# M7104BYA.net
KiCad netlist of a schematic drawn in EAGLE
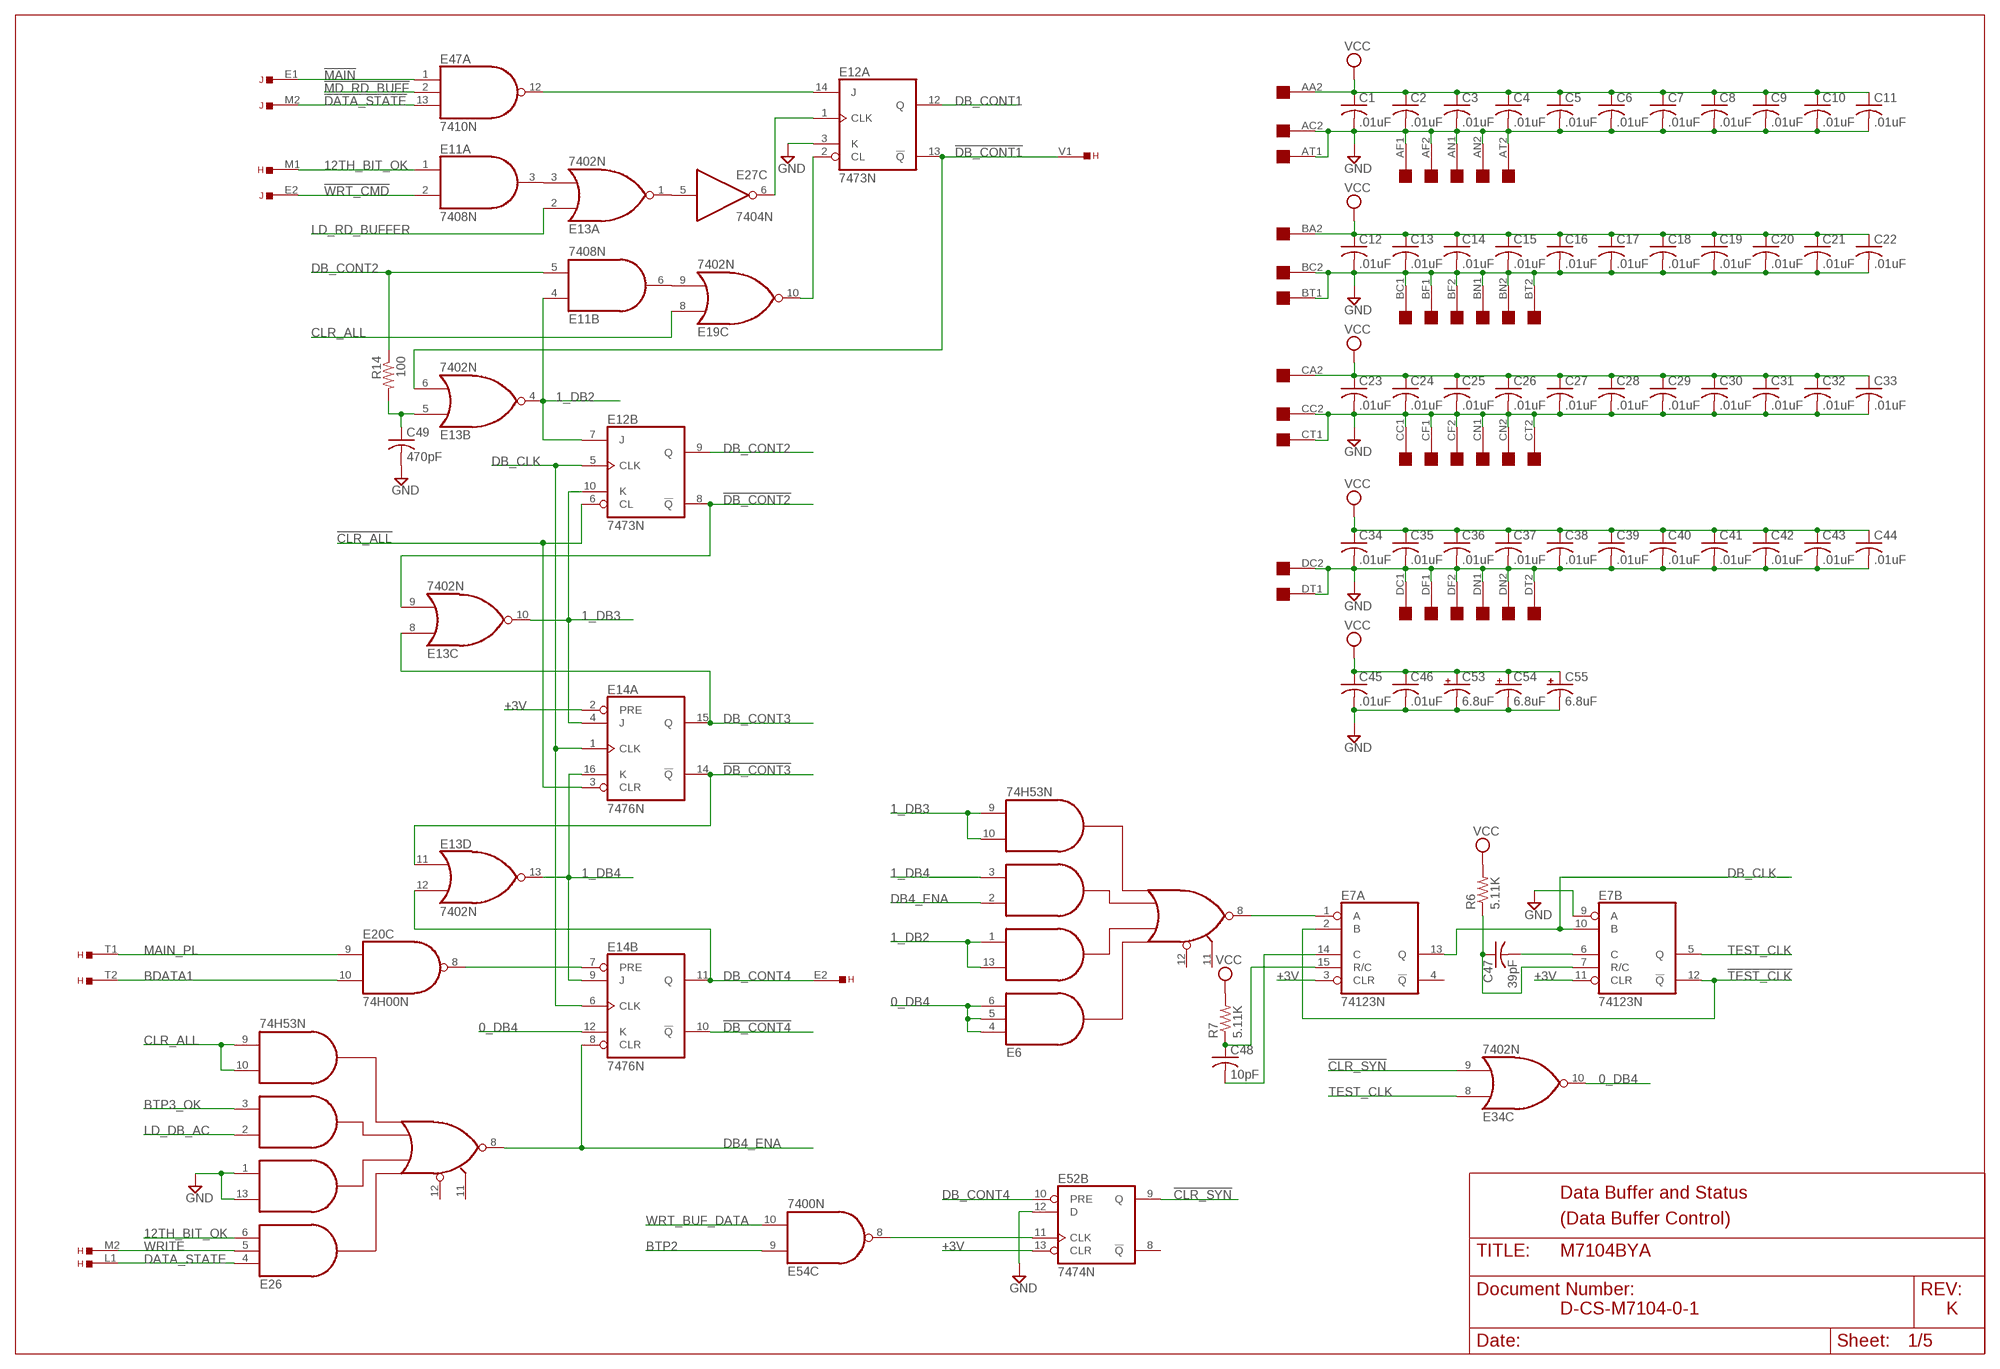
[diagram p0: schematic, sheet 1]
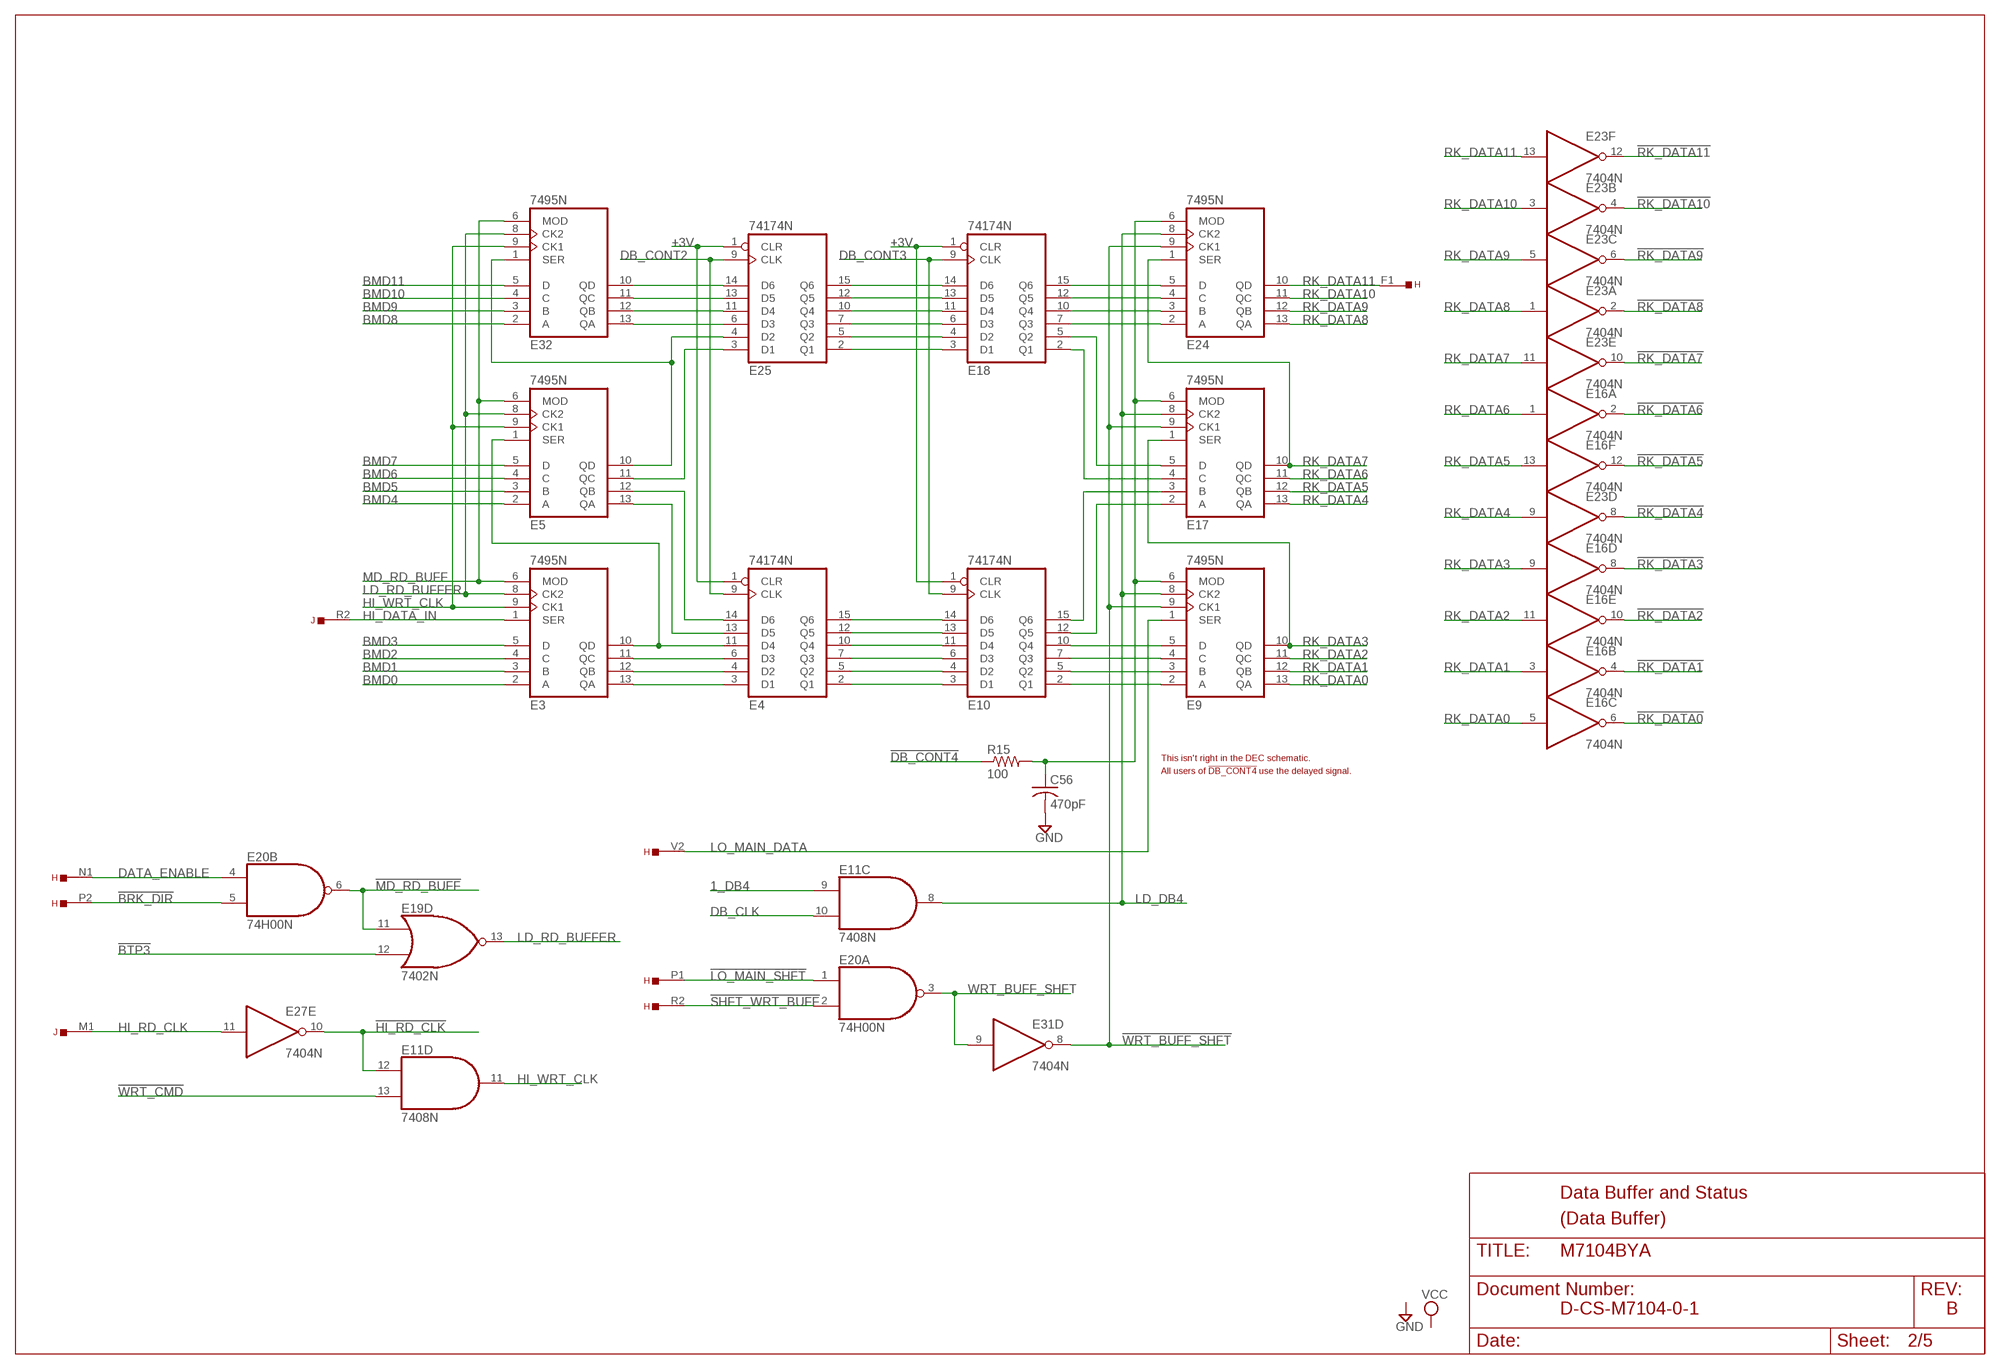
[diagram p1: schematic, sheet 2]
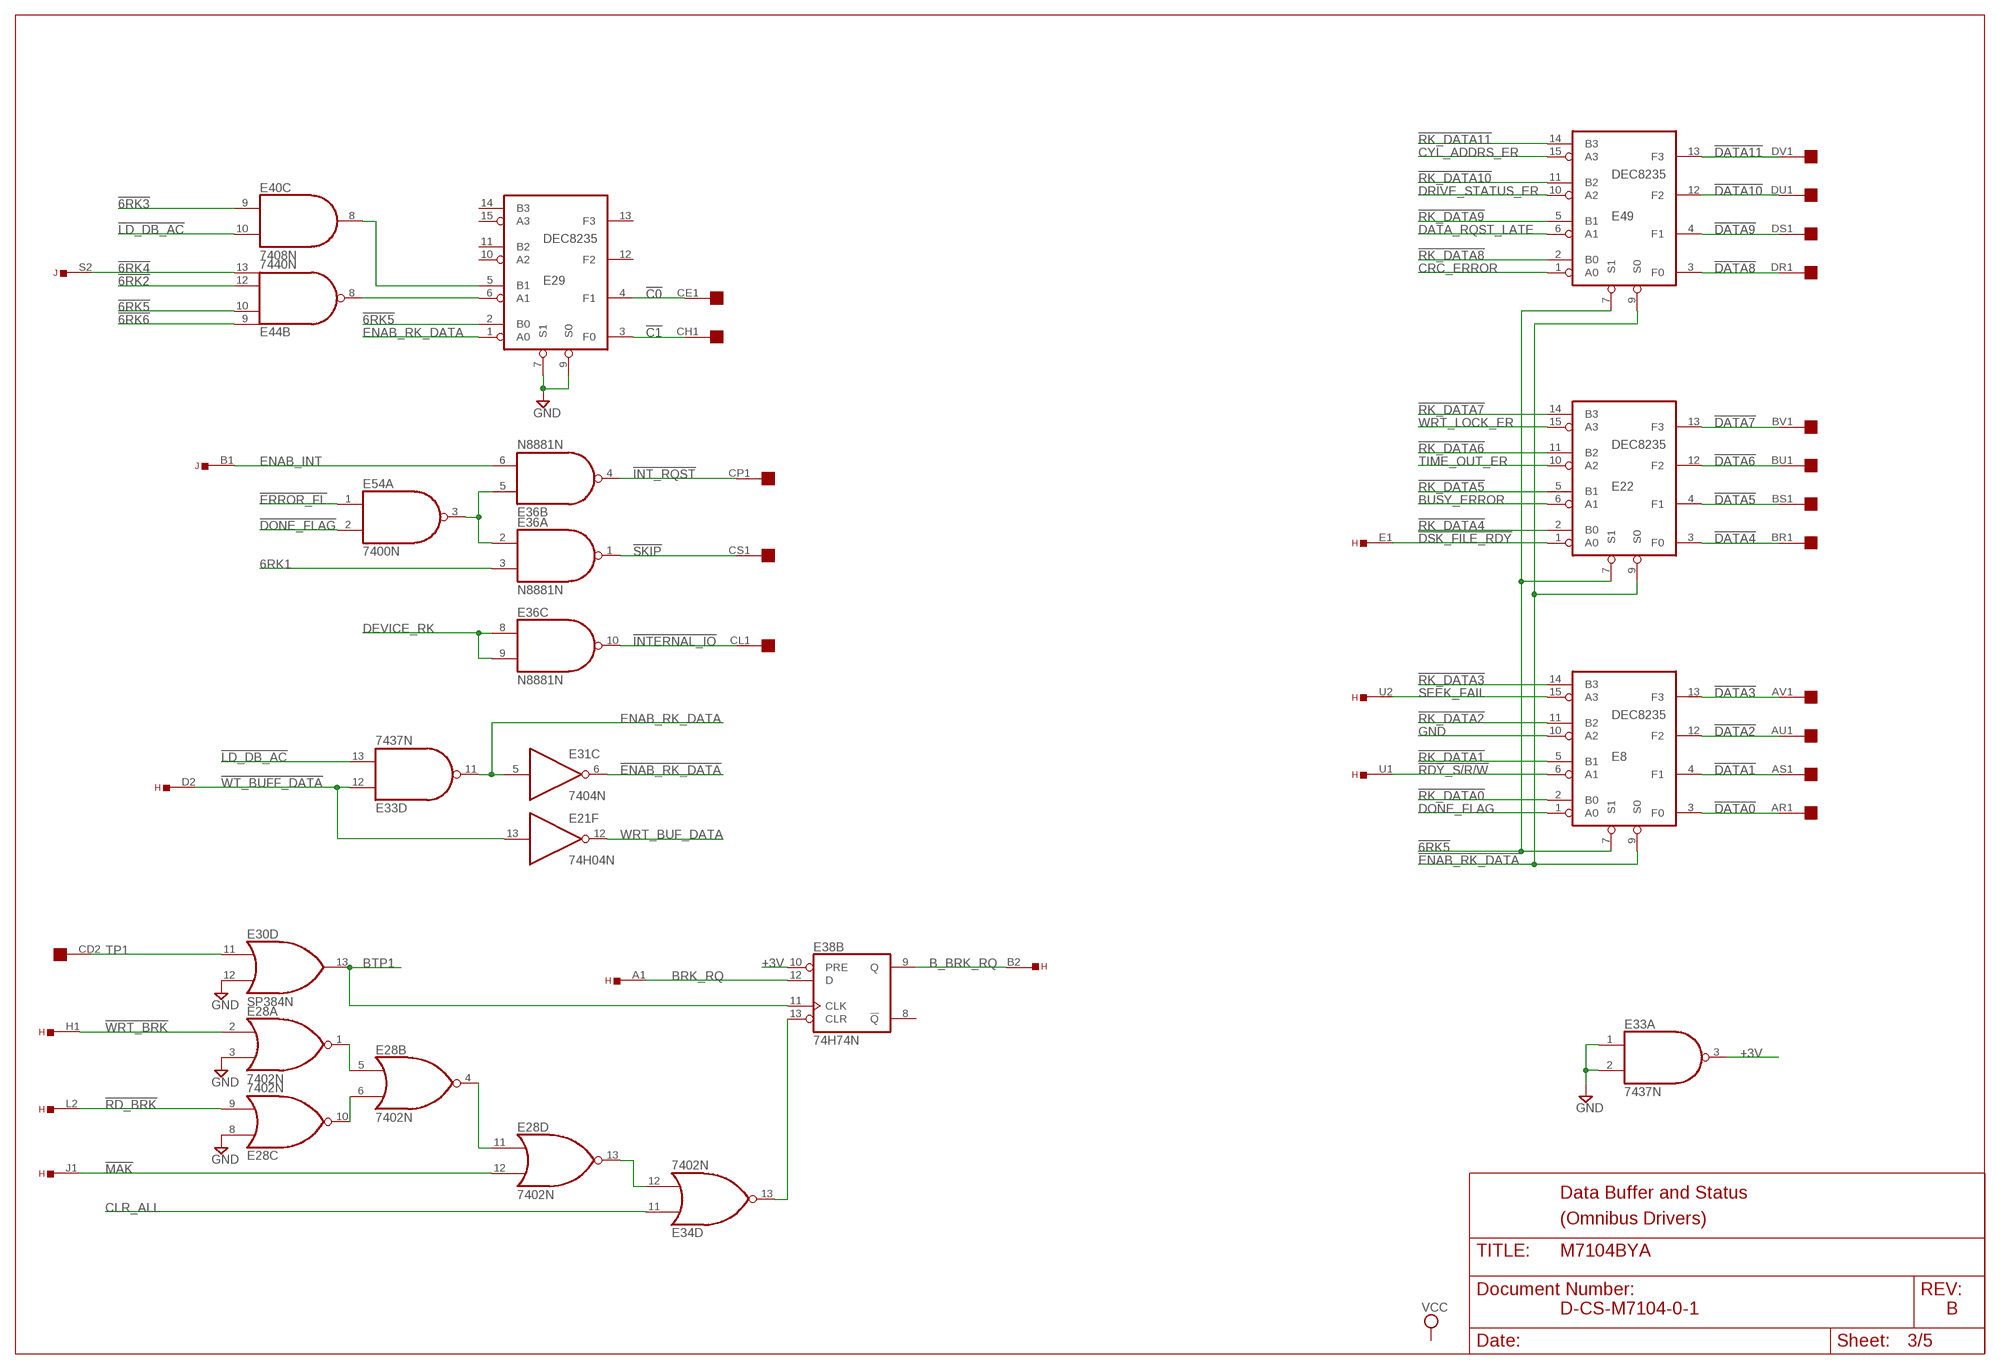
[diagram p2: schematic, sheet 3]
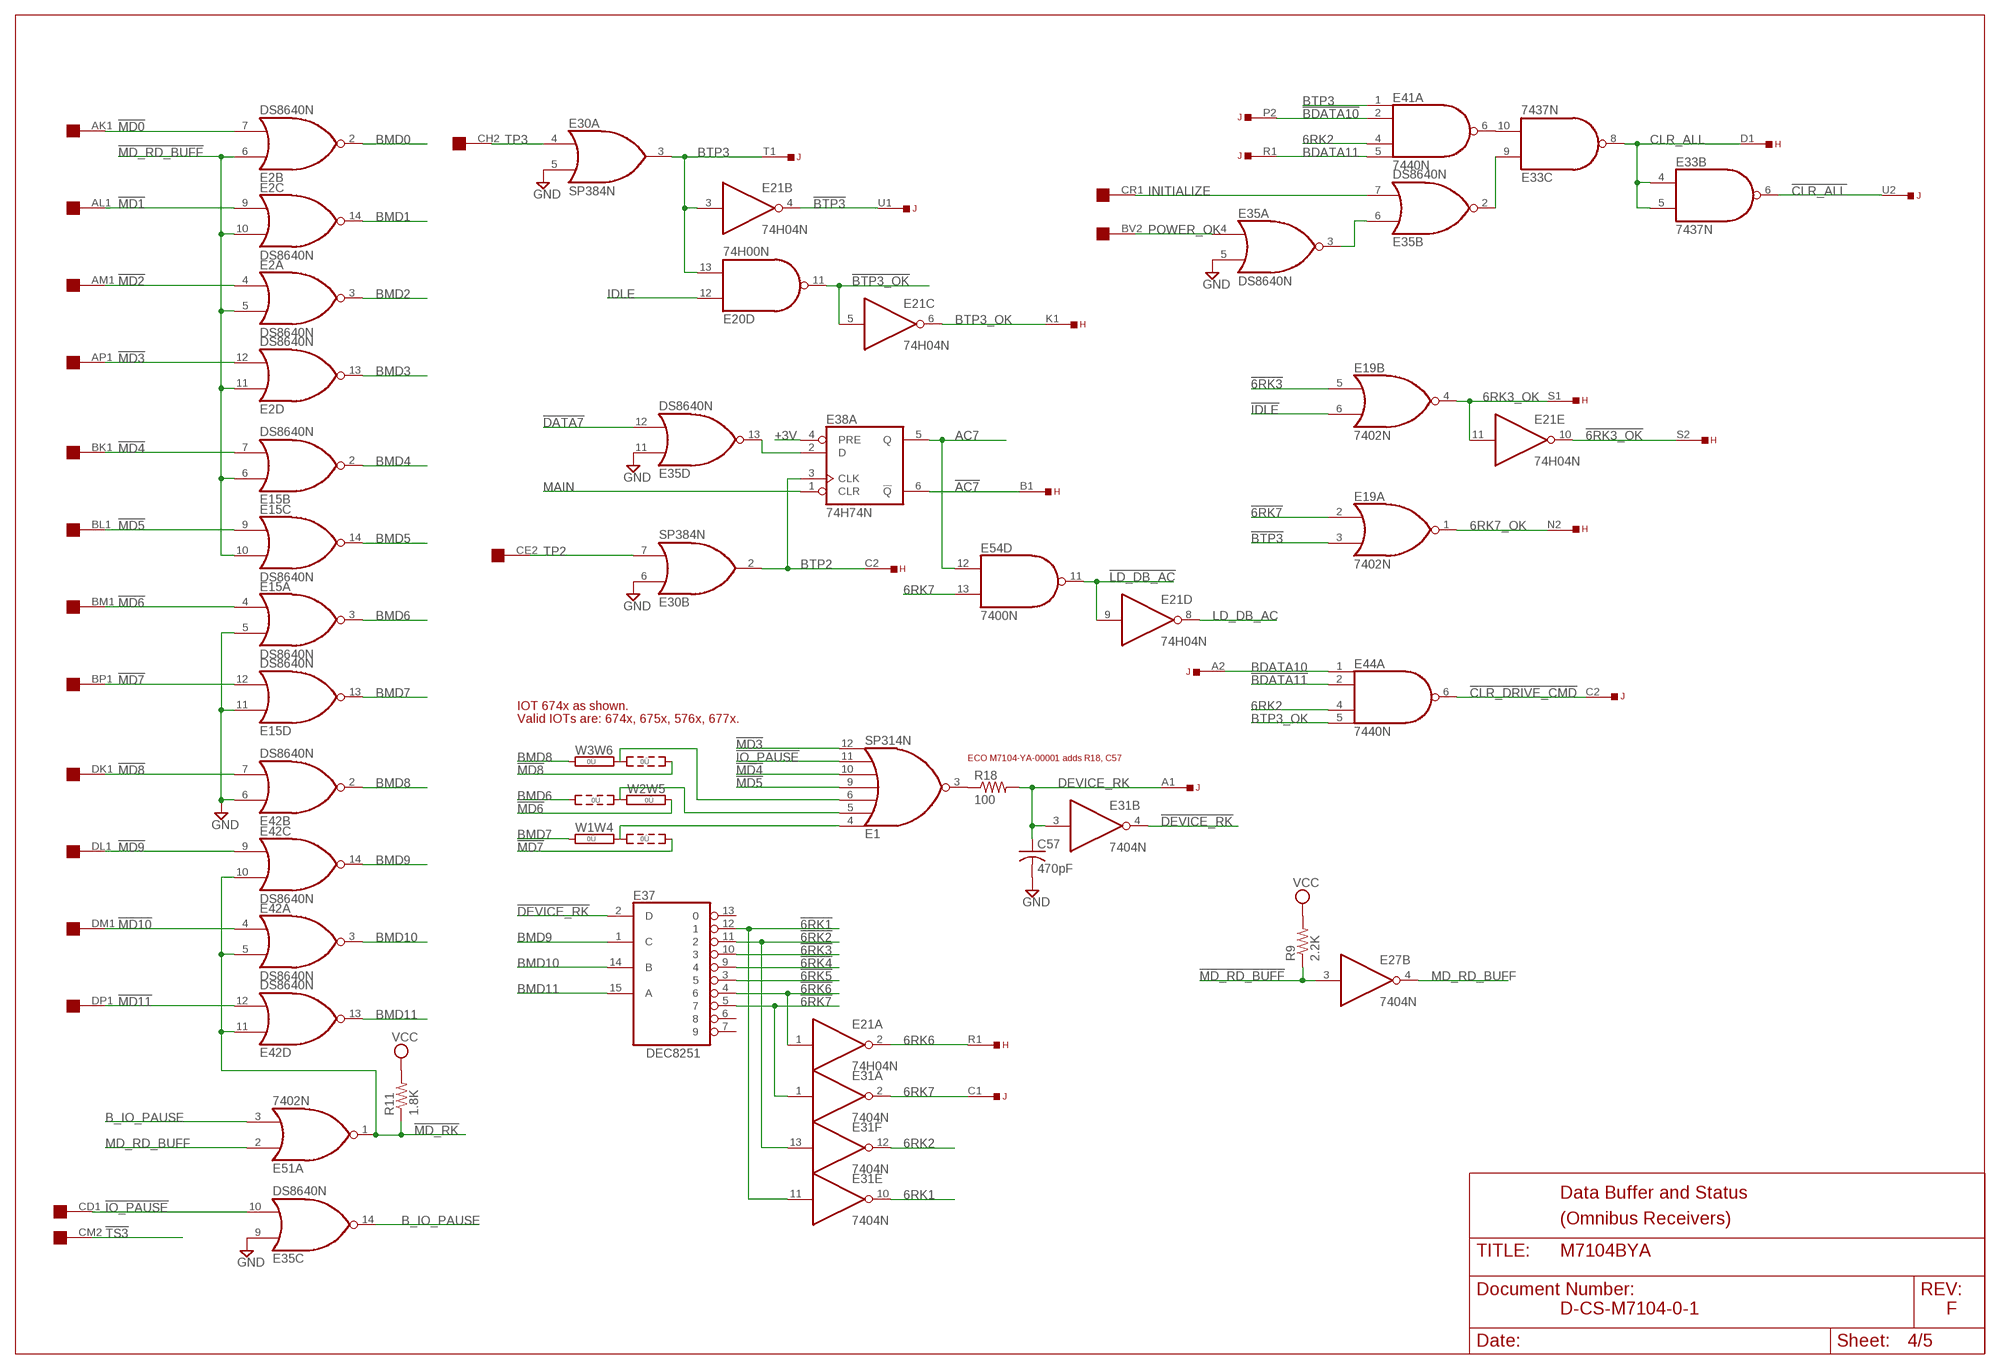
[diagram p3: schematic, sheet 4]
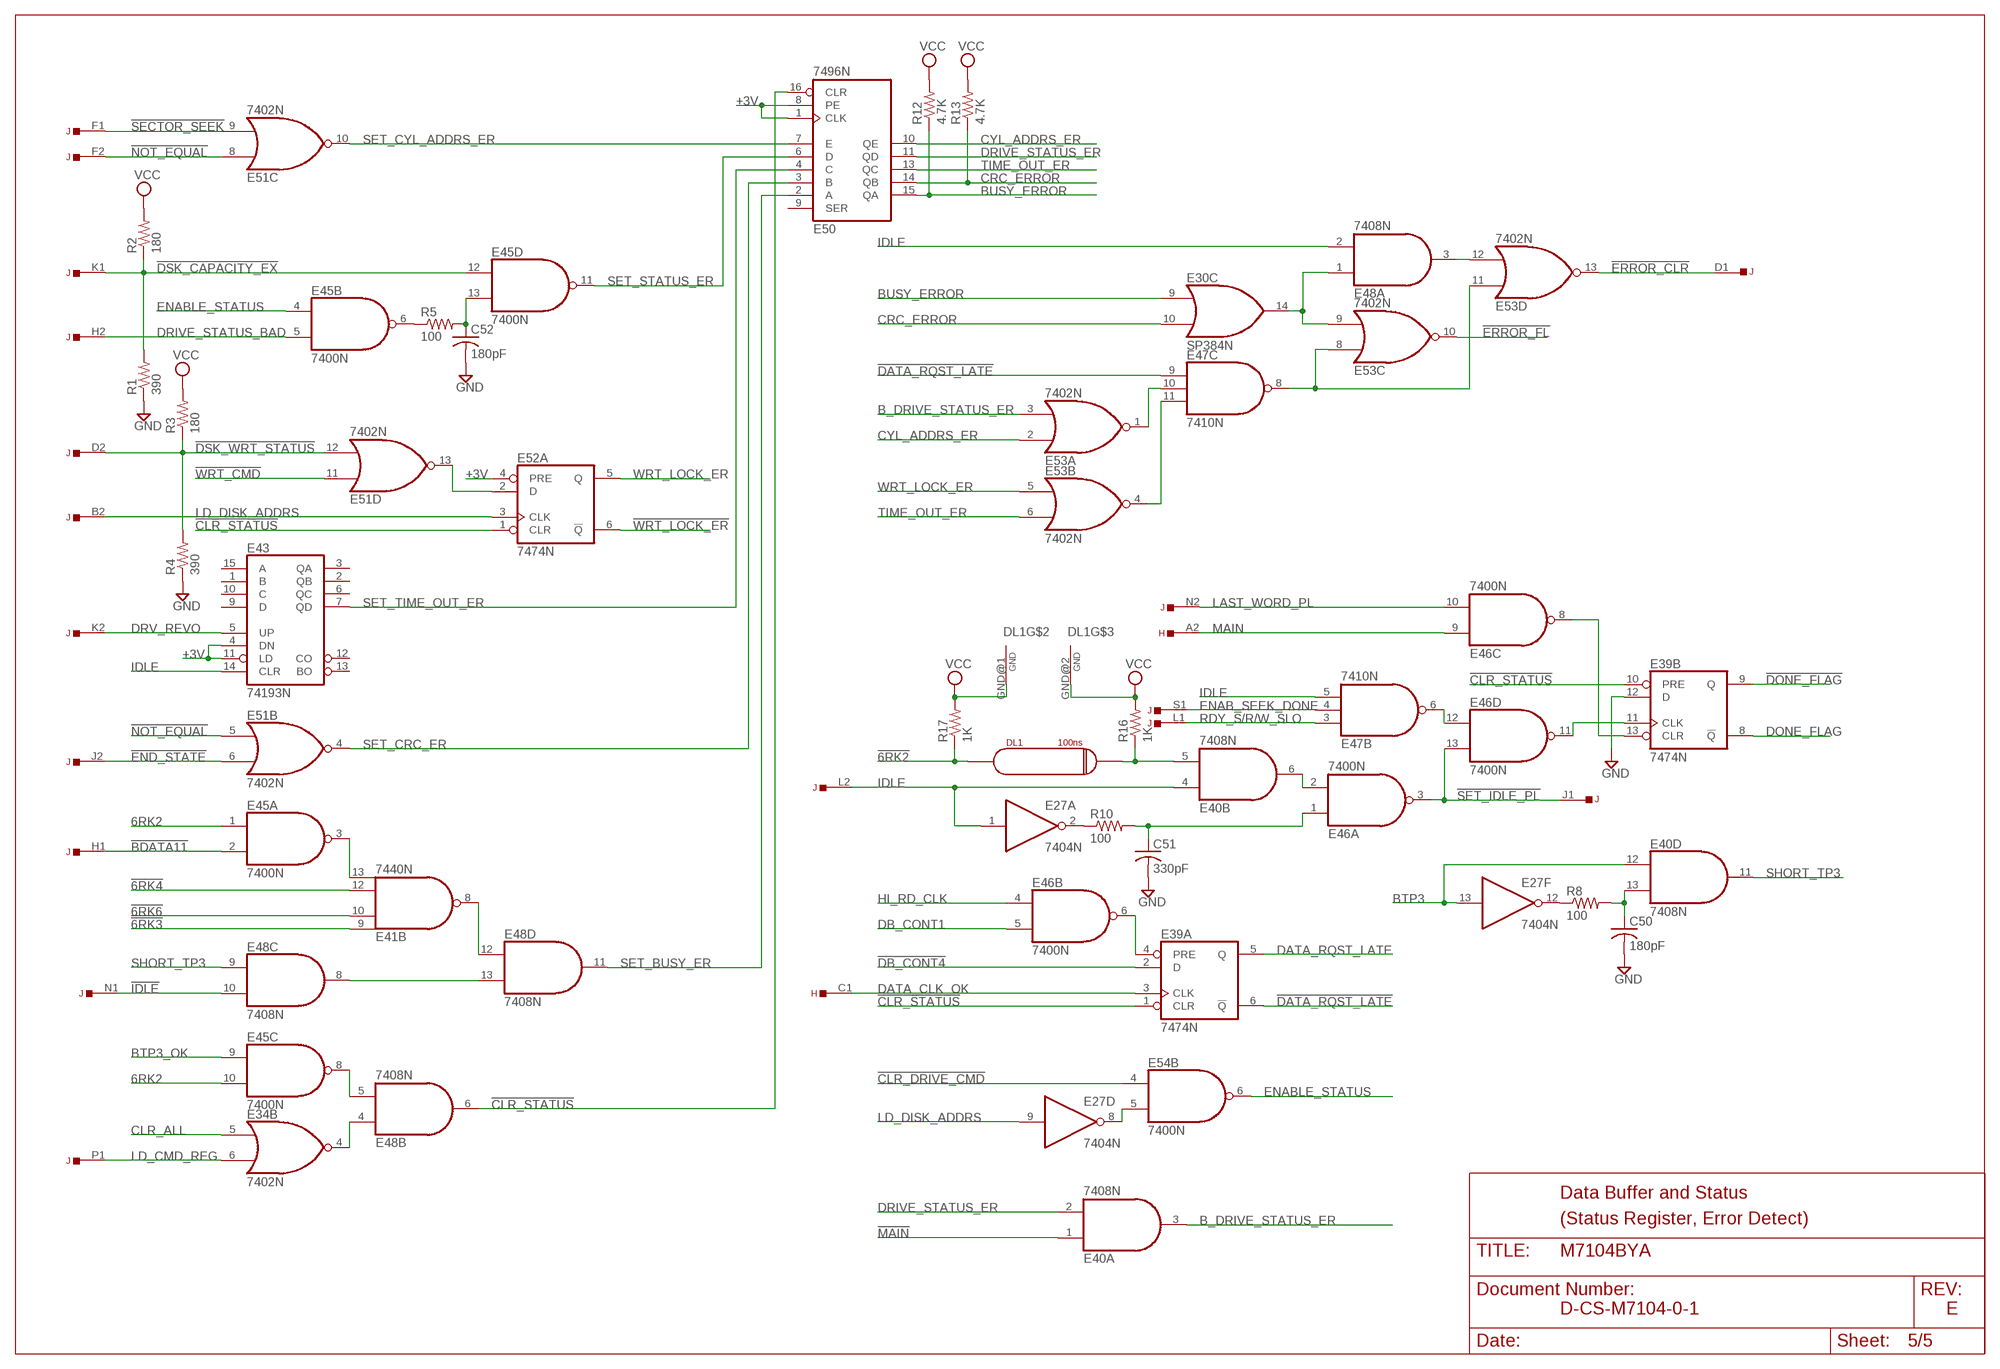
[diagram p4: schematic, sheet 5]

(export (version "E")
  (design (tool "Eeschema 10.0.6"))
  (components
    (comp (ref "C50")
      (value "180pF")
      (footprint "eagle-import:C063-025X075")
      (libsource (lib "eagle-import") (part "C-US"))
    )
    (comp (ref "C51")
      (value "330pF")
      (footprint "eagle-import:C063-025X075")
      (libsource (lib "eagle-import") (part "C-US"))
    )
    (comp (ref "C52")
      (value "180pF")
      (footprint "eagle-import:C063-025X075")
      (libsource (lib "eagle-import") (part "C-US"))
    )
    (comp (ref "DL1")
      (value "100ns")
      (footprint "eagle-import:RCL-L-XX-22")
      (libsource (lib "eagle-import") (part "RC-L-22"))
    )
    (comp (ref "E27")
      (value "7404N")
      (footprint "eagle-import:DIL14")
      (libsource (lib "eagle-import") (part "7404N"))
    )
    (comp (ref "E30")
      (value "SP384N")
      (footprint "eagle-import:DIL14")
      (libsource (lib "eagle-import") (part "SP384N"))
    )
    (comp (ref "E34")
      (value "7402N")
      (footprint "eagle-import:DIL14")
      (libsource (lib "eagle-import") (part "7402N"))
    )
    (comp (ref "E39")
      (value "7474N")
      (footprint "eagle-import:DIL14")
      (libsource (lib "eagle-import") (part "7474NS"))
    )
    (comp (ref "E40")
      (value "7408N")
      (footprint "eagle-import:DIL14")
      (libsource (lib "eagle-import") (part "7408NS"))
    )
    (comp (ref "E41")
      (value "7440N")
      (footprint "eagle-import:DIL14")
      (libsource (lib "eagle-import") (part "7440N"))
    )
    (comp (ref "E43")
      (value "74193N")
      (footprint "eagle-import:DIL16")
      (libsource (lib "eagle-import") (part "74193N"))
    )
    (comp (ref "E45")
      (value "7400N")
      (footprint "eagle-import:DIL14")
      (libsource (lib "eagle-import") (part "7400N"))
    )
    (comp (ref "E46")
      (value "7400N")
      (footprint "eagle-import:DIL14")
      (libsource (lib "eagle-import") (part "7400N"))
    )
    (comp (ref "E47")
      (value "7410N")
      (footprint "eagle-import:DIL14")
      (libsource (lib "eagle-import") (part "7410N"))
    )
    (comp (ref "E48")
      (value "7408N")
      (footprint "eagle-import:DIL14")
      (libsource (lib "eagle-import") (part "7408NS"))
    )
    (comp (ref "E50")
      (value "7496N")
      (footprint "eagle-import:DIL16")
      (libsource (lib "eagle-import") (part "7496NLS"))
    )
    (comp (ref "E51")
      (value "7402N")
      (footprint "eagle-import:DIL14")
      (libsource (lib "eagle-import") (part "7402N"))
    )
    (comp (ref "E52")
      (value "7474N")
      (footprint "eagle-import:DIL14")
      (libsource (lib "eagle-import") (part "7474NS"))
    )
    (comp (ref "E53")
      (value "7402N")
      (footprint "eagle-import:DIL14")
      (libsource (lib "eagle-import") (part "7402N"))
    )
    (comp (ref "E54")
      (value "7400N")
      (footprint "eagle-import:DIL14")
      (libsource (lib "eagle-import") (part "7400N"))
    )
    (comp (ref "H")
      (value "EDGE-TOP")
      (footprint "eagle-import:EDGE-CON2")
      (libsource (lib "eagle-import") (part "EDGE-TOP"))
    )
    (comp (ref "J")
      (value "EDGE-TOP")
      (footprint "eagle-import:EDGE-CON2")
      (libsource (lib "eagle-import") (part "EDGE-TOP"))
    )
    (comp (ref "R1")
      (value "390")
      (footprint "eagle-import:0207_10")
      (libsource (lib "eagle-import") (part "R-US_0207/10"))
    )
    (comp (ref "R2")
      (value "180")
      (footprint "eagle-import:0207_10")
      (libsource (lib "eagle-import") (part "R-US_0207/10"))
    )
    (comp (ref "R3")
      (value "180")
      (footprint "eagle-import:0207_10")
      (libsource (lib "eagle-import") (part "R-US_0207/10"))
    )
    (comp (ref "R4")
      (value "390")
      (footprint "eagle-import:0207_10")
      (libsource (lib "eagle-import") (part "R-US_0207/10"))
    )
    (comp (ref "R5")
      (value "100")
      (footprint "eagle-import:0207_10")
      (libsource (lib "eagle-import") (part "R-US_0207/10"))
    )
    (comp (ref "R8")
      (value "100")
      (footprint "eagle-import:0207_10")
      (libsource (lib "eagle-import") (part "R-US_0207/10"))
    )
    (comp (ref "R10")
      (value "100")
      (footprint "eagle-import:0207_10")
      (libsource (lib "eagle-import") (part "R-US_0207/10"))
    )
    (comp (ref "R12")
      (value "4.7K")
      (footprint "eagle-import:0207_10")
      (libsource (lib "eagle-import") (part "R-US_0207/10"))
    )
    (comp (ref "R13")
      (value "4.7K")
      (footprint "eagle-import:0207_10")
      (libsource (lib "eagle-import") (part "R-US_0207/10"))
    )
    (comp (ref "R16")
      (value "1K")
      (footprint "eagle-import:0207_10")
      (libsource (lib "eagle-import") (part "R-US_0207/10"))
    )
    (comp (ref "R17")
      (value "1K")
      (footprint "eagle-import:0207_10")
      (libsource (lib "eagle-import") (part "R-US_0207/10"))
    )
    (comp (ref "C57")
      (value "470pF")
      (footprint "eagle-import:C063-025X075")
      (libsource (lib "eagle-import") (part "C-US"))
    )
    (comp (ref "E1")
      (value "SP314N")
      (footprint "eagle-import:DIL14")
      (libsource (lib "eagle-import") (part "SP314N"))
    )
    (comp (ref "E2")
      (value "DS8640N")
      (footprint "eagle-import:DIL14")
      (libsource (lib "eagle-import") (part "DS8640N"))
    )
    (comp (ref "E15")
      (value "DS8640N")
      (footprint "eagle-import:DIL14")
      (libsource (lib "eagle-import") (part "DS8640N"))
    )
    (comp (ref "E19")
      (value "7402N")
      (footprint "eagle-import:DIL14")
      (libsource (lib "eagle-import") (part "7402N"))
    )
    (comp (ref "E20")
      (value "74H00N")
      (footprint "eagle-import:DIL14")
      (libsource (lib "eagle-import") (part "7400NS"))
    )
    (comp (ref "E21")
      (value "74H04N")
      (footprint "eagle-import:DIL14")
      (libsource (lib "eagle-import") (part "7404N"))
    )
    (comp (ref "E31")
      (value "7404N")
      (footprint "eagle-import:DIL14")
      (libsource (lib "eagle-import") (part "7404N"))
    )
    (comp (ref "E33")
      (value "7437N")
      (footprint "eagle-import:DIL14")
      (libsource (lib "eagle-import") (part "7437N"))
    )
    (comp (ref "E35")
      (value "DS8640N")
      (footprint "eagle-import:DIL14")
      (libsource (lib "eagle-import") (part "DS8640N"))
    )
    (comp (ref "E37")
      (value "DEC8251")
      (footprint "eagle-import:DIL16")
      (libsource (lib "eagle-import") (part "DEC8251"))
    )
    (comp (ref "E38")
      (value "74H74N")
      (footprint "eagle-import:DIL14")
      (libsource (lib "eagle-import") (part "7474NS"))
    )
    (comp (ref "E42")
      (value "DS8640N")
      (footprint "eagle-import:DIL14")
      (libsource (lib "eagle-import") (part "DS8640N"))
    )
    (comp (ref "E44")
      (value "7440N")
      (footprint "eagle-import:DIL14")
      (libsource (lib "eagle-import") (part "7440N"))
    )
    (comp (ref "OMNIBUS")
      (value "QUAD")
      (footprint "eagle-import:EDGE-CON8")
      (libsource (lib "eagle-import") (part "QUAD"))
    )
    (comp (ref "R9")
      (value "2.2K")
      (footprint "eagle-import:0207_10")
      (libsource (lib "eagle-import") (part "R-US_0207/10"))
    )
    (comp (ref "R11")
      (value "1.8K")
      (footprint "eagle-import:0207_10")
      (libsource (lib "eagle-import") (part "R-US_0207/10"))
    )
    (comp (ref "R18")
      (value "100")
      (footprint "eagle-import:0207_10")
      (libsource (lib "eagle-import") (part "R-US_0207/10"))
    )
    (comp (ref "W1W4")
      (value "0R2")
      (footprint "eagle-import:0R2_10")
      (libsource (lib "eagle-import") (part "0R2"))
    )
    (comp (ref "W2W5")
      (value "0R2")
      (footprint "eagle-import:0R2_10")
      (libsource (lib "eagle-import") (part "0R2"))
    )
    (comp (ref "W3W6")
      (value "0R2")
      (footprint "eagle-import:0R2_10")
      (libsource (lib "eagle-import") (part "0R2"))
    )
    (comp (ref "C1")
      (value ".01uF")
      (footprint "eagle-import:C063-025X075")
      (libsource (lib "eagle-import") (part "C-US"))
    )
    (comp (ref "C2")
      (value ".01uF")
      (footprint "eagle-import:C063-025X075")
      (libsource (lib "eagle-import") (part "C-US"))
    )
    (comp (ref "C3")
      (value ".01uF")
      (footprint "eagle-import:C063-025X075")
      (libsource (lib "eagle-import") (part "C-US"))
    )
    (comp (ref "C4")
      (value ".01uF")
      (footprint "eagle-import:C063-025X075")
      (libsource (lib "eagle-import") (part "C-US"))
    )
    (comp (ref "C5")
      (value ".01uF")
      (footprint "eagle-import:C063-025X075")
      (libsource (lib "eagle-import") (part "C-US"))
    )
    (comp (ref "C6")
      (value ".01uF")
      (footprint "eagle-import:C063-025X075")
      (libsource (lib "eagle-import") (part "C-US"))
    )
    (comp (ref "C7")
      (value ".01uF")
      (footprint "eagle-import:C063-025X075")
      (libsource (lib "eagle-import") (part "C-US"))
    )
    (comp (ref "C8")
      (value ".01uF")
      (footprint "eagle-import:C063-025X075")
      (libsource (lib "eagle-import") (part "C-US"))
    )
    (comp (ref "C9")
      (value ".01uF")
      (footprint "eagle-import:C063-025X075")
      (libsource (lib "eagle-import") (part "C-US"))
    )
    (comp (ref "C10")
      (value ".01uF")
      (footprint "eagle-import:C063-025X075")
      (libsource (lib "eagle-import") (part "C-US"))
    )
    (comp (ref "C11")
      (value ".01uF")
      (footprint "eagle-import:C063-025X075")
      (libsource (lib "eagle-import") (part "C-US"))
    )
    (comp (ref "C12")
      (value ".01uF")
      (footprint "eagle-import:C063-025X075")
      (libsource (lib "eagle-import") (part "C-US"))
    )
    (comp (ref "C13")
      (value ".01uF")
      (footprint "eagle-import:C063-025X075")
      (libsource (lib "eagle-import") (part "C-US"))
    )
    (comp (ref "C14")
      (value ".01uF")
      (footprint "eagle-import:C063-025X075")
      (libsource (lib "eagle-import") (part "C-US"))
    )
    (comp (ref "C15")
      (value ".01uF")
      (footprint "eagle-import:C063-025X075")
      (libsource (lib "eagle-import") (part "C-US"))
    )
    (comp (ref "C16")
      (value ".01uF")
      (footprint "eagle-import:C063-025X075")
      (libsource (lib "eagle-import") (part "C-US"))
    )
    (comp (ref "C17")
      (value ".01uF")
      (footprint "eagle-import:C063-025X075")
      (libsource (lib "eagle-import") (part "C-US"))
    )
    (comp (ref "C18")
      (value ".01uF")
      (footprint "eagle-import:C063-025X075")
      (libsource (lib "eagle-import") (part "C-US"))
    )
    (comp (ref "C19")
      (value ".01uF")
      (footprint "eagle-import:C063-025X075")
      (libsource (lib "eagle-import") (part "C-US"))
    )
    (comp (ref "C20")
      (value ".01uF")
      (footprint "eagle-import:C063-025X075")
      (libsource (lib "eagle-import") (part "C-US"))
    )
    (comp (ref "C21")
      (value ".01uF")
      (footprint "eagle-import:C063-025X075")
      (libsource (lib "eagle-import") (part "C-US"))
    )
    (comp (ref "C22")
      (value ".01uF")
      (footprint "eagle-import:C063-025X075")
      (libsource (lib "eagle-import") (part "C-US"))
    )
    (comp (ref "C23")
      (value ".01uF")
      (footprint "eagle-import:C063-025X075")
      (libsource (lib "eagle-import") (part "C-US"))
    )
    (comp (ref "C24")
      (value ".01uF")
      (footprint "eagle-import:C063-025X075")
      (libsource (lib "eagle-import") (part "C-US"))
    )
    (comp (ref "C25")
      (value ".01uF")
      (footprint "eagle-import:C063-025X075")
      (libsource (lib "eagle-import") (part "C-US"))
    )
    (comp (ref "C26")
      (value ".01uF")
      (footprint "eagle-import:C063-025X075")
      (libsource (lib "eagle-import") (part "C-US"))
    )
    (comp (ref "C27")
      (value ".01uF")
      (footprint "eagle-import:C063-025X075")
      (libsource (lib "eagle-import") (part "C-US"))
    )
    (comp (ref "C28")
      (value ".01uF")
      (footprint "eagle-import:C063-025X075")
      (libsource (lib "eagle-import") (part "C-US"))
    )
    (comp (ref "C29")
      (value ".01uF")
      (footprint "eagle-import:C063-025X075")
      (libsource (lib "eagle-import") (part "C-US"))
    )
    (comp (ref "C30")
      (value ".01uF")
      (footprint "eagle-import:C063-025X075")
      (libsource (lib "eagle-import") (part "C-US"))
    )
    (comp (ref "C31")
      (value ".01uF")
      (footprint "eagle-import:C063-025X075")
      (libsource (lib "eagle-import") (part "C-US"))
    )
    (comp (ref "C32")
      (value ".01uF")
      (footprint "eagle-import:C063-025X075")
      (libsource (lib "eagle-import") (part "C-US"))
    )
    (comp (ref "C33")
      (value ".01uF")
      (footprint "eagle-import:C063-025X075")
      (libsource (lib "eagle-import") (part "C-US"))
    )
    (comp (ref "C34")
      (value ".01uF")
      (footprint "eagle-import:C063-025X075")
      (libsource (lib "eagle-import") (part "C-US"))
    )
    (comp (ref "C35")
      (value ".01uF")
      (footprint "eagle-import:C063-025X075")
      (libsource (lib "eagle-import") (part "C-US"))
    )
    (comp (ref "C36")
      (value ".01uF")
      (footprint "eagle-import:C063-025X075")
      (libsource (lib "eagle-import") (part "C-US"))
    )
    (comp (ref "C37")
      (value ".01uF")
      (footprint "eagle-import:C063-025X075")
      (libsource (lib "eagle-import") (part "C-US"))
    )
    (comp (ref "C38")
      (value ".01uF")
      (footprint "eagle-import:C063-025X075")
      (libsource (lib "eagle-import") (part "C-US"))
    )
    (comp (ref "C39")
      (value ".01uF")
      (footprint "eagle-import:C063-025X075")
      (libsource (lib "eagle-import") (part "C-US"))
    )
    (comp (ref "C40")
      (value ".01uF")
      (footprint "eagle-import:C063-025X075")
      (libsource (lib "eagle-import") (part "C-US"))
    )
    (comp (ref "C41")
      (value ".01uF")
      (footprint "eagle-import:C063-025X075")
      (libsource (lib "eagle-import") (part "C-US"))
    )
    (comp (ref "C42")
      (value ".01uF")
      (footprint "eagle-import:C063-025X075")
      (libsource (lib "eagle-import") (part "C-US"))
    )
    (comp (ref "C43")
      (value ".01uF")
      (footprint "eagle-import:C063-025X075")
      (libsource (lib "eagle-import") (part "C-US"))
    )
    (comp (ref "C44")
      (value ".01uF")
      (footprint "eagle-import:C063-025X075")
      (libsource (lib "eagle-import") (part "C-US"))
    )
    (comp (ref "C45")
      (value ".01uF")
      (footprint "eagle-import:C063-025X075")
      (libsource (lib "eagle-import") (part "C-US"))
    )
    (comp (ref "C46")
      (value ".01uF")
      (footprint "eagle-import:C063-025X075")
      (libsource (lib "eagle-import") (part "C-US"))
    )
    (comp (ref "C47")
      (value "39pF")
      (footprint "eagle-import:C063-025X075")
      (libsource (lib "eagle-import") (part "C-US"))
    )
    (comp (ref "C48")
      (value "10pF")
      (footprint "eagle-import:C063-025X075")
      (libsource (lib "eagle-import") (part "C-US"))
    )
    (comp (ref "C49")
      (value "470pF")
      (footprint "eagle-import:C063-025X075")
      (libsource (lib "eagle-import") (part "C-US"))
    )
    (comp (ref "C53")
      (value "6.8uF")
      (footprint "eagle-import:E12-8")
      (libsource (lib "eagle-import") (part "CPOL-USE20-8AXIAL"))
    )
    (comp (ref "C54")
      (value "6.8uF")
      (footprint "eagle-import:E12-8")
      (libsource (lib "eagle-import") (part "CPOL-USE20-8AXIAL"))
    )
    (comp (ref "C55")
      (value "6.8uF")
      (footprint "eagle-import:E12-8")
      (libsource (lib "eagle-import") (part "CPOL-USE20-8AXIAL"))
    )
    (comp (ref "E6")
      (value "74H53N")
      (footprint "eagle-import:DIL14")
      (libsource (lib "eagle-import") (part "74H53N"))
    )
    (comp (ref "E7")
      (value "74123N")
      (footprint "eagle-import:DIL16")
      (libsource (lib "eagle-import") (part "74123N"))
    )
    (comp (ref "E11")
      (value "7408N")
      (footprint "eagle-import:DIL14")
      (libsource (lib "eagle-import") (part "7408NS"))
    )
    (comp (ref "E12")
      (value "7473N")
      (footprint "eagle-import:DIL14")
      (libsource (lib "eagle-import") (part "7473NLS"))
    )
    (comp (ref "E13")
      (value "7402N")
      (footprint "eagle-import:DIL14")
      (libsource (lib "eagle-import") (part "7402N"))
    )
    (comp (ref "E14")
      (value "7476N")
      (footprint "eagle-import:DIL16")
      (libsource (lib "eagle-import") (part "7476N"))
    )
    (comp (ref "E26")
      (value "74H53N")
      (footprint "eagle-import:DIL14")
      (libsource (lib "eagle-import") (part "74H53N"))
    )
    (comp (ref "R6")
      (value "5.11K")
      (footprint "eagle-import:0207_15")
      (libsource (lib "eagle-import") (part "R-US_0207/15"))
    )
    (comp (ref "R7")
      (value "5.11K")
      (footprint "eagle-import:0207_15")
      (libsource (lib "eagle-import") (part "R-US_0207/15"))
    )
    (comp (ref "R14")
      (value "100")
      (footprint "eagle-import:0207_10")
      (libsource (lib "eagle-import") (part "R-US_0207/10"))
    )
    (comp (ref "E8")
      (value "DEC8235")
      (footprint "eagle-import:DIL16")
      (libsource (lib "eagle-import") (part "DEC8235"))
    )
    (comp (ref "E22")
      (value "DEC8235")
      (footprint "eagle-import:DIL16")
      (libsource (lib "eagle-import") (part "DEC8235"))
    )
    (comp (ref "E28")
      (value "7402N")
      (footprint "eagle-import:DIL14")
      (libsource (lib "eagle-import") (part "7402N"))
    )
    (comp (ref "E29")
      (value "DEC8235")
      (footprint "eagle-import:DIL16")
      (libsource (lib "eagle-import") (part "DEC8235"))
    )
    (comp (ref "E36")
      (value "N8881N")
      (footprint "eagle-import:DIL14")
      (libsource (lib "eagle-import") (part "N8881N"))
    )
    (comp (ref "E49")
      (value "DEC8235")
      (footprint "eagle-import:DIL16")
      (libsource (lib "eagle-import") (part "DEC8235"))
    )
    (comp (ref "C56")
      (value "470pF")
      (footprint "eagle-import:C063-025X075")
      (libsource (lib "eagle-import") (part "C-US"))
    )
    (comp (ref "E3")
      (value "7495N")
      (footprint "eagle-import:DIL14")
      (libsource (lib "eagle-import") (part "7495N"))
    )
    (comp (ref "E4")
      (value "74174N")
      (footprint "eagle-import:DIL16")
      (libsource (lib "eagle-import") (part "74174N"))
    )
    (comp (ref "E5")
      (value "7495N")
      (footprint "eagle-import:DIL14")
      (libsource (lib "eagle-import") (part "7495N"))
    )
    (comp (ref "E9")
      (value "7495N")
      (footprint "eagle-import:DIL14")
      (libsource (lib "eagle-import") (part "7495N"))
    )
    (comp (ref "E10")
      (value "74174N")
      (footprint "eagle-import:DIL16")
      (libsource (lib "eagle-import") (part "74174N"))
    )
    (comp (ref "E16")
      (value "7404N")
      (footprint "eagle-import:DIL14")
      (libsource (lib "eagle-import") (part "7404N"))
    )
    (comp (ref "E17")
      (value "7495N")
      (footprint "eagle-import:DIL14")
      (libsource (lib "eagle-import") (part "7495N"))
    )
    (comp (ref "E18")
      (value "74174N")
      (footprint "eagle-import:DIL16")
      (libsource (lib "eagle-import") (part "74174N"))
    )
    (comp (ref "E23")
      (value "7404N")
      (footprint "eagle-import:DIL14")
      (libsource (lib "eagle-import") (part "7404N"))
    )
    (comp (ref "E24")
      (value "7495N")
      (footprint "eagle-import:DIL14")
      (libsource (lib "eagle-import") (part "7495N"))
    )
    (comp (ref "E25")
      (value "74174N")
      (footprint "eagle-import:DIL16")
      (libsource (lib "eagle-import") (part "74174N"))
    )
    (comp (ref "E32")
      (value "7495N")
      (footprint "eagle-import:DIL14")
      (libsource (lib "eagle-import") (part "7495N"))
    )
    (comp (ref "R15")
      (value "100")
      (footprint "eagle-import:0207_10")
      (libsource (lib "eagle-import") (part "R-US_0207/10"))
    )
  )
  (nets
    (net (code "1") (name "+3V") (class "Default")
      (node (ref "E10") (pin "1") (pinfunction "CLR_1") (pintype "input"))
      (node (ref "E14") (pin "2") (pinfunction "PRE_2") (pintype "input"))
      (node (ref "E18") (pin "1") (pinfunction "CLR_1") (pintype "input"))
      (node (ref "E25") (pin "1") (pinfunction "CLR_1") (pintype "input"))
      (node (ref "E33") (pin "3") (pinfunction "O_3") (pintype "output"))
      (node (ref "E38") (pin "10") (pinfunction "PRE_10") (pintype "input"))
      (node (ref "E38") (pin "4") (pinfunction "PRE_4") (pintype "input"))
      (node (ref "E4") (pin "1") (pinfunction "CLR_1") (pintype "input"))
      (node (ref "E43") (pin "11") (pinfunction "LD_11") (pintype "input"))
      (node (ref "E43") (pin "4") (pinfunction "DN_4") (pintype "input"))
      (node (ref "E50") (pin "1") (pinfunction "CLK_1") (pintype "input"))
      (node (ref "E50") (pin "8") (pinfunction "PE_8") (pintype "input"))
      (node (ref "E52") (pin "13") (pinfunction "CLR_13") (pintype "input"))
      (node (ref "E52") (pin "4") (pinfunction "PRE_4") (pintype "input"))
      (node (ref "E7") (pin "11") (pinfunction "CLR_11") (pintype "input"))
      (node (ref "E7") (pin "3") (pinfunction "CLR_3") (pintype "input"))
    )
    (net (code "2") (name "0_DB4") (class "Default")
      (node (ref "E14") (pin "12") (pinfunction "K_12") (pintype "input"))
      (node (ref "E34") (pin "10") (pinfunction "O_10") (pintype "output"))
      (node (ref "E6") (pin "4") (pinfunction "I1_4") (pintype "input"))
      (node (ref "E6") (pin "5") (pinfunction "I11_5") (pintype "input"))
      (node (ref "E6") (pin "6") (pinfunction "I2_6") (pintype "input"))
    )
    (net (code "3") (name "1_DB2") (class "Default")
      (node (ref "E11") (pin "4") (pinfunction "I0_4") (pintype "input"))
      (node (ref "E12") (pin "7") (pinfunction "J_7") (pintype "input"))
      (node (ref "E13") (pin "4") (pinfunction "O_4") (pintype "output"))
      (node (ref "E6") (pin "1") (pinfunction "I4_1") (pintype "input"))
      (node (ref "E6") (pin "13") (pinfunction "I3_13") (pintype "input"))
    )
    (net (code "4") (name "1_DB3") (class "Default")
      (node (ref "E12") (pin "10") (pinfunction "K_10") (pintype "input"))
      (node (ref "E13") (pin "10") (pinfunction "O_10") (pintype "output"))
      (node (ref "E14") (pin "4") (pinfunction "J_4") (pintype "input"))
      (node (ref "E6") (pin "10") (pinfunction "I7_10") (pintype "input"))
      (node (ref "E6") (pin "9") (pinfunction "I8_9") (pintype "input"))
    )
    (net (code "5") (name "1_DB4") (class "Default")
      (node (ref "E11") (pin "9") (pinfunction "I0_9") (pintype "input"))
      (node (ref "E13") (pin "13") (pinfunction "O_13") (pintype "output"))
      (node (ref "E14") (pin "16") (pinfunction "K_16") (pintype "input"))
      (node (ref "E14") (pin "9") (pinfunction "J_9") (pintype "input"))
      (node (ref "E6") (pin "3") (pinfunction "I6_3") (pintype "input"))
    )
    (net (code "6") (name "6RK1") (class "Default")
      (node (ref "E31") (pin "10") (pinfunction "O_10") (pintype "output"))
      (node (ref "E36") (pin "3") (pinfunction "I1_3") (pintype "input"))
    )
    (net (code "7") (name "6RK2") (class "Default")
      (node (ref "E31") (pin "12") (pinfunction "O_12") (pintype "output"))
      (node (ref "E41") (pin "4") (pinfunction "I2_4") (pintype "input"))
      (node (ref "E44") (pin "4") (pinfunction "I2_4") (pintype "input"))
      (node (ref "E45") (pin "1") (pinfunction "I0_1") (pintype "input"))
      (node (ref "E45") (pin "10") (pinfunction "I1_10") (pintype "input"))
    )
    (net (code "8") (name "6RK3_OK") (class "Default")
      (node (ref "E19") (pin "4") (pinfunction "O_4") (pintype "output"))
      (node (ref "E21") (pin "11") (pinfunction "I_11") (pintype "input"))
      (node (ref "H") (pin "S1") (pinfunction "P_S1") (pintype "passive"))
    )
    (net (code "9") (name "6RK6") (class "Default")
      (node (ref "E21") (pin "2") (pinfunction "O_2") (pintype "output"))
      (node (ref "H") (pin "R1") (pinfunction "P_R1") (pintype "passive"))
    )
    (net (code "10") (name "6RK7") (class "Default")
      (node (ref "E31") (pin "2") (pinfunction "O_2") (pintype "output"))
      (node (ref "E54") (pin "13") (pinfunction "I1_13") (pintype "input"))
      (node (ref "J") (pin "C1") (pinfunction "P_C1") (pintype "passive"))
    )
    (net (code "11") (name "6RK7_OK") (class "Default")
      (node (ref "E19") (pin "1") (pinfunction "O_1") (pintype "output"))
      (node (ref "H") (pin "N2") (pinfunction "P_N2") (pintype "passive"))
    )
    (net (code "12") (name "12TH_BIT_OK") (class "Default")
      (node (ref "E11") (pin "1") (pinfunction "I0_1") (pintype "input"))
      (node (ref "E26") (pin "6") (pinfunction "I2_6") (pintype "input"))
      (node (ref "H") (pin "M1") (pinfunction "P_M1") (pintype "passive"))
    )
    (net (code "13") (name "AC7") (class "Default")
      (node (ref "E38") (pin "5") (pinfunction "Q_5") (pintype "output"))
      (node (ref "E54") (pin "12") (pinfunction "I0_12") (pintype "input"))
    )
    (net (code "14") (name "BDATA1") (class "Default")
      (node (ref "E20") (pin "10") (pinfunction "I1_10") (pintype "input"))
      (node (ref "H") (pin "T2") (pinfunction "P_T2") (pintype "passive"))
    )
    (net (code "15") (name "BDATA10") (class "Default")
      (node (ref "E44") (pin "1") (pinfunction "I0_1") (pintype "input"))
      (node (ref "J") (pin "A2") (pinfunction "P_A2") (pintype "passive"))
    )
    (net (code "16") (name "BDATA11") (class "Default")
      (node (ref "E41") (pin "5") (pinfunction "I3_5") (pintype "input"))
      (node (ref "J") (pin "R1") (pinfunction "P_R1") (pintype "passive"))
    )
    (net (code "17") (name "BMD0") (class "Default")
      (node (ref "E2") (pin "2") (pinfunction "O_2") (pintype "output"))
      (node (ref "E3") (pin "2") (pinfunction "A_2") (pintype "input"))
    )
    (net (code "18") (name "BMD1") (class "Default")
      (node (ref "E2") (pin "14") (pinfunction "O_14") (pintype "output"))
      (node (ref "E3") (pin "3") (pinfunction "B_3") (pintype "input"))
    )
    (net (code "19") (name "BMD2") (class "Default")
      (node (ref "E2") (pin "3") (pinfunction "O_3") (pintype "output"))
      (node (ref "E3") (pin "4") (pinfunction "C_4") (pintype "input"))
    )
    (net (code "20") (name "BMD3") (class "Default")
      (node (ref "E2") (pin "13") (pinfunction "O_13") (pintype "output"))
      (node (ref "E3") (pin "5") (pinfunction "D_5") (pintype "input"))
    )
    (net (code "21") (name "BMD4") (class "Default")
      (node (ref "E15") (pin "2") (pinfunction "O_2") (pintype "output"))
      (node (ref "E5") (pin "2") (pinfunction "A_2") (pintype "input"))
    )
    (net (code "22") (name "BMD5") (class "Default")
      (node (ref "E15") (pin "14") (pinfunction "O_14") (pintype "output"))
      (node (ref "E5") (pin "3") (pinfunction "B_3") (pintype "input"))
    )
    (net (code "23") (name "BMD6") (class "Default")
      (node (ref "E15") (pin "3") (pinfunction "O_3") (pintype "output"))
      (node (ref "E5") (pin "4") (pinfunction "C_4") (pintype "input"))
      (node (ref "W2W5") (pin "3") (pinfunction "3_3") (pintype "passive"))
    )
    (net (code "24") (name "BMD7") (class "Default")
      (node (ref "E15") (pin "13") (pinfunction "O_13") (pintype "output"))
      (node (ref "E5") (pin "5") (pinfunction "D_5") (pintype "input"))
      (node (ref "W1W4") (pin "1") (pinfunction "1_1") (pintype "passive"))
    )
    (net (code "25") (name "BMD8") (class "Default")
      (node (ref "E32") (pin "2") (pinfunction "A_2") (pintype "input"))
      (node (ref "E42") (pin "2") (pinfunction "O_2") (pintype "output"))
      (node (ref "W3W6") (pin "1") (pinfunction "1_1") (pintype "passive"))
    )
    (net (code "26") (name "BMD9") (class "Default")
      (node (ref "E32") (pin "3") (pinfunction "B_3") (pintype "input"))
      (node (ref "E37") (pin "1") (pinfunction "C_1") (pintype "input"))
      (node (ref "E42") (pin "14") (pinfunction "O_14") (pintype "output"))
    )
    (net (code "27") (name "BMD10") (class "Default")
      (node (ref "E32") (pin "4") (pinfunction "C_4") (pintype "input"))
      (node (ref "E37") (pin "14") (pinfunction "B_14") (pintype "input"))
      (node (ref "E42") (pin "3") (pinfunction "O_3") (pintype "output"))
    )
    (net (code "28") (name "BMD11") (class "Default")
      (node (ref "E32") (pin "5") (pinfunction "D_5") (pintype "input"))
      (node (ref "E37") (pin "15") (pinfunction "A_15") (pintype "input"))
      (node (ref "E42") (pin "13") (pinfunction "O_13") (pintype "output"))
    )
    (net (code "29") (name "BRK_RQ") (class "Default")
      (node (ref "E38") (pin "12") (pinfunction "D_12") (pintype "input"))
      (node (ref "H") (pin "A1") (pinfunction "P_A1") (pintype "passive"))
    )
    (net (code "30") (name "BTP1") (class "Default")
      (node (ref "E30") (pin "13") (pinfunction "O_13") (pintype "output"))
      (node (ref "E38") (pin "11") (pinfunction "CLK_11") (pintype "input"))
    )
    (net (code "31") (name "BTP2") (class "Default")
      (node (ref "E30") (pin "2") (pinfunction "O_2") (pintype "output"))
      (node (ref "E38") (pin "3") (pinfunction "CLK_3") (pintype "input"))
      (node (ref "E54") (pin "9") (pinfunction "I0_9") (pintype "input"))
      (node (ref "H") (pin "C2") (pinfunction "P_C2") (pintype "passive"))
    )
    (net (code "32") (name "BTP3") (class "Default")
      (node (ref "E20") (pin "13") (pinfunction "I1_13") (pintype "input"))
      (node (ref "E21") (pin "3") (pinfunction "I_3") (pintype "input"))
      (node (ref "E27") (pin "13") (pinfunction "I_13") (pintype "input"))
      (node (ref "E30") (pin "3") (pinfunction "O_3") (pintype "output"))
      (node (ref "E40") (pin "12") (pinfunction "I0_12") (pintype "input"))
      (node (ref "E41") (pin "1") (pinfunction "I0_1") (pintype "input"))
      (node (ref "J") (pin "T1") (pinfunction "P_T1") (pintype "passive"))
    )
    (net (code "33") (name "BTP3_OK") (class "Default")
      (node (ref "E21") (pin "6") (pinfunction "O_6") (pintype "output"))
      (node (ref "E26") (pin "3") (pinfunction "I6_3") (pintype "input"))
      (node (ref "E44") (pin "5") (pinfunction "I3_5") (pintype "input"))
      (node (ref "E45") (pin "9") (pinfunction "I0_9") (pintype "input"))
      (node (ref "H") (pin "K1") (pinfunction "P_K1") (pintype "passive"))
    )
    (net (code "34") (name "BUSY_ERROR") (class "Default")
      (node (ref "E22") (pin "6") (pinfunction "A1_6") (pintype "input"))
      (node (ref "E30") (pin "9") (pinfunction "I0_9") (pintype "input"))
      (node (ref "E50") (pin "15") (pinfunction "QA_15") (pintype "output"))
      (node (ref "R12") (pin "1") (pinfunction "1_1") (pintype "passive"))
    )
    (net (code "35") (name "B_BRK_RQ") (class "Default")
      (node (ref "E38") (pin "9") (pinfunction "Q_9") (pintype "output"))
      (node (ref "H") (pin "B2") (pinfunction "P_B2") (pintype "passive"))
    )
    (net (code "36") (name "B_DRIVE_STATUS_ER") (class "Default")
      (node (ref "E40") (pin "3") (pinfunction "O_3") (pintype "output"))
      (node (ref "E53") (pin "3") (pinfunction "I1_3") (pintype "input"))
    )
    (net (code "37") (name "B_IO_PAUSE") (class "Default")
      (node (ref "E35") (pin "14") (pinfunction "O_14") (pintype "output"))
      (node (ref "E51") (pin "3") (pinfunction "I1_3") (pintype "input"))
    )
    (net (code "38") (name "CLR_ALL") (class "Default")
      (node (ref "E19") (pin "8") (pinfunction "I0_8") (pintype "input"))
      (node (ref "E26") (pin "10") (pinfunction "I7_10") (pintype "input"))
      (node (ref "E26") (pin "9") (pinfunction "I8_9") (pintype "input"))
      (node (ref "E33") (pin "4") (pinfunction "I0_4") (pintype "input"))
      (node (ref "E33") (pin "5") (pinfunction "I1_5") (pintype "input"))
      (node (ref "E33") (pin "8") (pinfunction "O_8") (pintype "output"))
      (node (ref "E34") (pin "11") (pinfunction "I0_11") (pintype "input"))
      (node (ref "E34") (pin "5") (pinfunction "I0_5") (pintype "input"))
      (node (ref "H") (pin "D1") (pinfunction "P_D1") (pintype "passive"))
    )
    (net (code "39") (name "CRC_ERROR") (class "Default")
      (node (ref "E30") (pin "10") (pinfunction "I1_10") (pintype "input"))
      (node (ref "E49") (pin "1") (pinfunction "A0_1") (pintype "input"))
      (node (ref "E50") (pin "14") (pinfunction "QB_14") (pintype "output"))
      (node (ref "R13") (pin "1") (pinfunction "1_1") (pintype "passive"))
    )
    (net (code "40") (name "CYL_ADDRS_ER") (class "Default")
      (node (ref "E49") (pin "15") (pinfunction "A3_15") (pintype "input"))
      (node (ref "E50") (pin "10") (pinfunction "QE_10") (pintype "output"))
      (node (ref "E53") (pin "2") (pinfunction "I0_2") (pintype "input"))
    )
    (net (code "41") (name "DATA_CLK_OK") (class "Default")
      (node (ref "E39") (pin "3") (pinfunction "CLK_3") (pintype "input"))
      (node (ref "H") (pin "C1") (pinfunction "P_C1") (pintype "passive"))
    )
    (net (code "42") (name "DATA_ENABLE") (class "Default")
      (node (ref "E20") (pin "4") (pinfunction "I0_4") (pintype "input"))
      (node (ref "H") (pin "N1") (pinfunction "P_N1") (pintype "passive"))
    )
    (net (code "43") (name "DATA_RQST_LATE") (class "Default")
      (node (ref "E39") (pin "5") (pinfunction "Q_5") (pintype "output"))
      (node (ref "E49") (pin "6") (pinfunction "A1_6") (pintype "input"))
    )
    (net (code "44") (name "DATA_STATE") (class "Default")
      (node (ref "E26") (pin "4") (pinfunction "I1_4") (pintype "input"))
      (node (ref "H") (pin "L1") (pinfunction "P_L1") (pintype "passive"))
    )
    (net (code "45") (name "DB4_ENA") (class "Default")
      (node (ref "E14") (pin "8") (pinfunction "CLR_8") (pintype "input"))
      (node (ref "E26") (pin "8") (pinfunction "O_8") (pintype "output"))
      (node (ref "E6") (pin "2") (pinfunction "I5_2") (pintype "input"))
    )
    (net (code "46") (name "DB_CLK") (class "Default")
      (node (ref "E11") (pin "10") (pinfunction "I1_10") (pintype "input"))
      (node (ref "E12") (pin "5") (pinfunction "CLK_5") (pintype "input"))
      (node (ref "E14") (pin "1") (pinfunction "CLK_1") (pintype "input"))
      (node (ref "E14") (pin "6") (pinfunction "CLK_6") (pintype "input"))
      (node (ref "E7") (pin "10") (pinfunction "B_10") (pintype "input"))
      (node (ref "E7") (pin "13") (pinfunction "Q_13") (pintype "output"))
    )
    (net (code "47") (name "DB_CONT1") (class "Default")
      (node (ref "E12") (pin "12") (pinfunction "Q_12") (pintype "output"))
      (node (ref "E46") (pin "5") (pinfunction "I1_5") (pintype "input"))
    )
    (net (code "48") (name "DB_CONT2") (class "Default")
      (node (ref "E11") (pin "5") (pinfunction "I1_5") (pintype "input"))
      (node (ref "E12") (pin "9") (pinfunction "Q_9") (pintype "output"))
      (node (ref "E25") (pin "9") (pinfunction "CLK_9") (pintype "input"))
      (node (ref "E4") (pin "9") (pinfunction "CLK_9") (pintype "input"))
      (node (ref "R14") (pin "1") (pinfunction "1_1") (pintype "passive"))
    )
    (net (code "49") (name "DB_CONT3") (class "Default")
      (node (ref "E10") (pin "9") (pinfunction "CLK_9") (pintype "input"))
      (node (ref "E13") (pin "8") (pinfunction "I0_8") (pintype "input"))
      (node (ref "E14") (pin "15") (pinfunction "Q_15") (pintype "output"))
      (node (ref "E18") (pin "9") (pinfunction "CLK_9") (pintype "input"))
    )
    (net (code "50") (name "DB_CONT4") (class "Default")
      (node (ref "E13") (pin "12") (pinfunction "I1_12") (pintype "input"))
      (node (ref "E14") (pin "11") (pinfunction "Q_11") (pintype "output"))
      (node (ref "E52") (pin "10") (pinfunction "PRE_10") (pintype "input"))
      (node (ref "H") (pin "E2") (pinfunction "P_E2") (pintype "passive"))
    )
    (net (code "51") (name "DEVICE_RK") (class "Default")
      (node (ref "C57") (pin "1") (pinfunction "1_1") (pintype "passive"))
      (node (ref "E31") (pin "3") (pinfunction "I_3") (pintype "input"))
      (node (ref "E36") (pin "8") (pinfunction "I0_8") (pintype "input"))
      (node (ref "E36") (pin "9") (pinfunction "I1_9") (pintype "input"))
      (node (ref "J") (pin "A1") (pinfunction "P_A1") (pintype "passive"))
      (node (ref "R18") (pin "2") (pinfunction "2_2") (pintype "passive"))
    )
    (net (code "52") (name "DONE_FLAG") (class "Default")
      (node (ref "E39") (pin "8") (pinfunction "~{Q}_8") (pintype "output"))
      (node (ref "E8") (pin "1") (pinfunction "A0_1") (pintype "input"))
    )
    (net (code "53") (name "DRIVE_STATUS_BAD") (class "Default")
      (node (ref "E45") (pin "5") (pinfunction "I1_5") (pintype "input"))
      (node (ref "J") (pin "H2") (pinfunction "P_H2") (pintype "passive"))
    )
    (net (code "54") (name "DRIVE_STATUS_ER") (class "Default")
      (node (ref "E40") (pin "2") (pinfunction "I1_2") (pintype "input"))
      (node (ref "E49") (pin "10") (pinfunction "A2_10") (pintype "input"))
      (node (ref "E50") (pin "11") (pinfunction "QD_11") (pintype "output"))
    )
    (net (code "55") (name "DRV_REVO") (class "Default")
      (node (ref "E43") (pin "5") (pinfunction "UP_5") (pintype "input"))
      (node (ref "J") (pin "K2") (pinfunction "P_K2") (pintype "passive"))
    )
    (net (code "56") (name "ENABLE_STATUS") (class "Default")
      (node (ref "E45") (pin "4") (pinfunction "I0_4") (pintype "input"))
      (node (ref "E54") (pin "6") (pinfunction "O_6") (pintype "output"))
    )
    (net (code "57") (name "ENAB_INT") (class "Default")
      (node (ref "E36") (pin "6") (pinfunction "I1_6") (pintype "input"))
      (node (ref "J") (pin "B1") (pinfunction "P_B1") (pintype "passive"))
    )
    (net (code "58") (name "ENAB_RK_DATA") (class "Default")
      (node (ref "E29") (pin "1") (pinfunction "A0_1") (pintype "input"))
      (node (ref "E31") (pin "5") (pinfunction "I_5") (pintype "input"))
      (node (ref "E33") (pin "11") (pinfunction "O_11") (pintype "output"))
    )
    (net (code "59") (name "ENAB_SEEK_DONE") (class "Default")
      (node (ref "E47") (pin "4") (pinfunction "I1_4") (pintype "input"))
      (node (ref "J") (pin "S1") (pinfunction "P_S1") (pintype "passive"))
    )
    (net (code "60") (name "GND") (class "Default")
      (node (ref "C1") (pin "2") (pinfunction "2_2") (pintype "passive"))
      (node (ref "C10") (pin "2") (pinfunction "2_2") (pintype "passive"))
      (node (ref "C11") (pin "2") (pinfunction "2_2") (pintype "passive"))
      (node (ref "C12") (pin "2") (pinfunction "2_2") (pintype "passive"))
      (node (ref "C13") (pin "2") (pinfunction "2_2") (pintype "passive"))
      (node (ref "C14") (pin "2") (pinfunction "2_2") (pintype "passive"))
      (node (ref "C15") (pin "2") (pinfunction "2_2") (pintype "passive"))
      (node (ref "C16") (pin "2") (pinfunction "2_2") (pintype "passive"))
      (node (ref "C17") (pin "2") (pinfunction "2_2") (pintype "passive"))
      (node (ref "C18") (pin "2") (pinfunction "2_2") (pintype "passive"))
      (node (ref "C19") (pin "2") (pinfunction "2_2") (pintype "passive"))
      (node (ref "C2") (pin "2") (pinfunction "2_2") (pintype "passive"))
      (node (ref "C20") (pin "2") (pinfunction "2_2") (pintype "passive"))
      (node (ref "C21") (pin "2") (pinfunction "2_2") (pintype "passive"))
      (node (ref "C22") (pin "2") (pinfunction "2_2") (pintype "passive"))
      (node (ref "C23") (pin "2") (pinfunction "2_2") (pintype "passive"))
      (node (ref "C24") (pin "2") (pinfunction "2_2") (pintype "passive"))
      (node (ref "C25") (pin "2") (pinfunction "2_2") (pintype "passive"))
      (node (ref "C26") (pin "2") (pinfunction "2_2") (pintype "passive"))
      (node (ref "C27") (pin "2") (pinfunction "2_2") (pintype "passive"))
      (node (ref "C28") (pin "2") (pinfunction "2_2") (pintype "passive"))
      (node (ref "C29") (pin "2") (pinfunction "2_2") (pintype "passive"))
      (node (ref "C3") (pin "2") (pinfunction "2_2") (pintype "passive"))
      (node (ref "C30") (pin "2") (pinfunction "2_2") (pintype "passive"))
      (node (ref "C31") (pin "2") (pinfunction "2_2") (pintype "passive"))
      (node (ref "C32") (pin "2") (pinfunction "2_2") (pintype "passive"))
      (node (ref "C33") (pin "2") (pinfunction "2_2") (pintype "passive"))
      (node (ref "C34") (pin "2") (pinfunction "2_2") (pintype "passive"))
      (node (ref "C35") (pin "2") (pinfunction "2_2") (pintype "passive"))
      (node (ref "C36") (pin "2") (pinfunction "2_2") (pintype "passive"))
      (node (ref "C37") (pin "2") (pinfunction "2_2") (pintype "passive"))
      (node (ref "C38") (pin "2") (pinfunction "2_2") (pintype "passive"))
      (node (ref "C39") (pin "2") (pinfunction "2_2") (pintype "passive"))
      (node (ref "C4") (pin "2") (pinfunction "2_2") (pintype "passive"))
      (node (ref "C40") (pin "2") (pinfunction "2_2") (pintype "passive"))
      (node (ref "C41") (pin "2") (pinfunction "2_2") (pintype "passive"))
      (node (ref "C42") (pin "2") (pinfunction "2_2") (pintype "passive"))
      (node (ref "C43") (pin "2") (pinfunction "2_2") (pintype "passive"))
      (node (ref "C44") (pin "2") (pinfunction "2_2") (pintype "passive"))
      (node (ref "C45") (pin "2") (pinfunction "2_2") (pintype "passive"))
      (node (ref "C46") (pin "2") (pinfunction "2_2") (pintype "passive"))
      (node (ref "C49") (pin "2") (pinfunction "2_2") (pintype "passive"))
      (node (ref "C5") (pin "2") (pinfunction "2_2") (pintype "passive"))
      (node (ref "C50") (pin "2") (pinfunction "2_2") (pintype "passive"))
      (node (ref "C51") (pin "2") (pinfunction "2_2") (pintype "passive"))
      (node (ref "C52") (pin "2") (pinfunction "2_2") (pintype "passive"))
      (node (ref "C53") (pin "-") (pinfunction "-_-") (pintype "passive"))
      (node (ref "C54") (pin "-") (pinfunction "-_-") (pintype "passive"))
      (node (ref "C55") (pin "-") (pinfunction "-_-") (pintype "passive"))
      (node (ref "C56") (pin "2") (pinfunction "2_2") (pintype "passive"))
      (node (ref "C57") (pin "2") (pinfunction "2_2") (pintype "passive"))
      (node (ref "C6") (pin "2") (pinfunction "2_2") (pintype "passive"))
      (node (ref "C7") (pin "2") (pinfunction "2_2") (pintype "passive"))
      (node (ref "C8") (pin "2") (pinfunction "2_2") (pintype "passive"))
      (node (ref "C9") (pin "2") (pinfunction "2_2") (pintype "passive"))
      (node (ref "E12") (pin "3") (pinfunction "K_3") (pintype "input"))
      (node (ref "E15") (pin "11") (pinfunction "I0_11") (pintype "input"))
      (node (ref "E15") (pin "5") (pinfunction "I1_5") (pintype "input"))
      (node (ref "E26") (pin "1") (pinfunction "I4_1") (pintype "input"))
      (node (ref "E26") (pin "13") (pinfunction "I3_13") (pintype "input"))
      (node (ref "E28") (pin "3") (pinfunction "I1_3") (pintype "input"))
      (node (ref "E28") (pin "8") (pinfunction "I0_8") (pintype "input"))
      (node (ref "E29") (pin "7") (pinfunction "S1_7") (pintype "input"))
      (node (ref "E29") (pin "9") (pinfunction "S0_9") (pintype "input"))
      (node (ref "E30") (pin "12") (pinfunction "I1_12") (pintype "input"))
      (node (ref "E30") (pin "5") (pinfunction "I1_5") (pintype "input"))
      (node (ref "E30") (pin "6") (pinfunction "I0_6") (pintype "input"))
      (node (ref "E33") (pin "1") (pinfunction "I0_1") (pintype "input"))
      (node (ref "E33") (pin "2") (pinfunction "I1_2") (pintype "input"))
      (node (ref "E35") (pin "11") (pinfunction "I0_11") (pintype "input"))
      (node (ref "E35") (pin "5") (pinfunction "I1_5") (pintype "input"))
      (node (ref "E35") (pin "9") (pinfunction "I0_9") (pintype "input"))
      (node (ref "E39") (pin "12") (pinfunction "D_12") (pintype "input"))
      (node (ref "E42") (pin "6") (pinfunction "I0_6") (pintype "input"))
      (node (ref "E52") (pin "12") (pinfunction "D_12") (pintype "input"))
      (node (ref "E7") (pin "9") (pinfunction "A_9") (pintype "input"))
      (node (ref "E8") (pin "10") (pinfunction "A2_10") (pintype "input"))
      (node (ref "OMNIBUS") (pin "AC2") (pinfunction "1_AC2") (pintype "bidirectional"))
      (node (ref "OMNIBUS") (pin "AF1") (pinfunction "1_AF1") (pintype "bidirectional"))
      (node (ref "OMNIBUS") (pin "AF2") (pinfunction "1_AF2") (pintype "bidirectional"))
      (node (ref "OMNIBUS") (pin "AN1") (pinfunction "1_AN1") (pintype "bidirectional"))
      (node (ref "OMNIBUS") (pin "AN2") (pinfunction "1_AN2") (pintype "bidirectional"))
      (node (ref "OMNIBUS") (pin "AT1") (pinfunction "1_AT1") (pintype "bidirectional"))
      (node (ref "OMNIBUS") (pin "AT2") (pinfunction "1_AT2") (pintype "bidirectional"))
      (node (ref "OMNIBUS") (pin "BC1") (pinfunction "1_BC1") (pintype "bidirectional"))
      (node (ref "OMNIBUS") (pin "BC2") (pinfunction "1_BC2") (pintype "bidirectional"))
      (node (ref "OMNIBUS") (pin "BF1") (pinfunction "1_BF1") (pintype "bidirectional"))
      (node (ref "OMNIBUS") (pin "BF2") (pinfunction "1_BF2") (pintype "bidirectional"))
      (node (ref "OMNIBUS") (pin "BN1") (pinfunction "1_BN1") (pintype "bidirectional"))
      (node (ref "OMNIBUS") (pin "BN2") (pinfunction "1_BN2") (pintype "bidirectional"))
      (node (ref "OMNIBUS") (pin "BT1") (pinfunction "1_BT1") (pintype "bidirectional"))
      (node (ref "OMNIBUS") (pin "BT2") (pinfunction "1_BT2") (pintype "bidirectional"))
      (node (ref "OMNIBUS") (pin "CC1") (pinfunction "1_CC1") (pintype "bidirectional"))
      (node (ref "OMNIBUS") (pin "CC2") (pinfunction "1_CC2") (pintype "bidirectional"))
      (node (ref "OMNIBUS") (pin "CF1") (pinfunction "1_CF1") (pintype "bidirectional"))
      (node (ref "OMNIBUS") (pin "CF2") (pinfunction "1_CF2") (pintype "bidirectional"))
      (node (ref "OMNIBUS") (pin "CN1") (pinfunction "1_CN1") (pintype "bidirectional"))
      (node (ref "OMNIBUS") (pin "CN2") (pinfunction "1_CN2") (pintype "bidirectional"))
      (node (ref "OMNIBUS") (pin "CT1") (pinfunction "1_CT1") (pintype "bidirectional"))
      (node (ref "OMNIBUS") (pin "CT2") (pinfunction "1_CT2") (pintype "bidirectional"))
      (node (ref "OMNIBUS") (pin "DC1") (pinfunction "1_DC1") (pintype "bidirectional"))
      (node (ref "OMNIBUS") (pin "DC2") (pinfunction "1_DC2") (pintype "bidirectional"))
      (node (ref "OMNIBUS") (pin "DF1") (pinfunction "1_DF1") (pintype "bidirectional"))
      (node (ref "OMNIBUS") (pin "DF2") (pinfunction "1_DF2") (pintype "bidirectional"))
      (node (ref "OMNIBUS") (pin "DN1") (pinfunction "1_DN1") (pintype "bidirectional"))
      (node (ref "OMNIBUS") (pin "DN2") (pinfunction "1_DN2") (pintype "bidirectional"))
      (node (ref "OMNIBUS") (pin "DT1") (pinfunction "1_DT1") (pintype "bidirectional"))
      (node (ref "OMNIBUS") (pin "DT2") (pinfunction "1_DT2") (pintype "bidirectional"))
      (node (ref "R1") (pin "1") (pinfunction "1_1") (pintype "passive"))
      (node (ref "R4") (pin "1") (pinfunction "1_1") (pintype "passive"))
    )
    (net (code "61") (name "HI_DATA_IN") (class "Default")
      (node (ref "E3") (pin "1") (pinfunction "SER_1") (pintype "input"))
      (node (ref "J") (pin "R2") (pinfunction "P_R2") (pintype "passive"))
    )
    (net (code "62") (name "HI_RD_CLK") (class "Default")
      (node (ref "E27") (pin "11") (pinfunction "I_11") (pintype "input"))
      (node (ref "E46") (pin "4") (pinfunction "I0_4") (pintype "input"))
      (node (ref "J") (pin "M1") (pinfunction "P_M1") (pintype "passive"))
    )
    (net (code "63") (name "HI_WRT_CLK") (class "Default")
      (node (ref "E11") (pin "11") (pinfunction "O_11") (pintype "output"))
      (node (ref "E3") (pin "9") (pinfunction "CK1_9") (pintype "input"))
      (node (ref "E32") (pin "9") (pinfunction "CK1_9") (pintype "input"))
      (node (ref "E5") (pin "9") (pinfunction "CK1_9") (pintype "input"))
    )
    (net (code "64") (name "IDLE") (class "Default")
      (node (ref "E20") (pin "12") (pinfunction "I0_12") (pintype "input"))
      (node (ref "E27") (pin "1") (pinfunction "I_1") (pintype "input"))
      (node (ref "E40") (pin "4") (pinfunction "I0_4") (pintype "input"))
      (node (ref "E43") (pin "14") (pinfunction "CLR_14") (pintype "input"))
      (node (ref "E47") (pin "5") (pinfunction "I2_5") (pintype "input"))
      (node (ref "E48") (pin "2") (pinfunction "I1_2") (pintype "input"))
      (node (ref "J") (pin "L2") (pinfunction "P_L2") (pintype "passive"))
    )
    (net (code "65") (name "INITIALIZE") (class "Default")
      (node (ref "E35") (pin "7") (pinfunction "I1_7") (pintype "input"))
      (node (ref "OMNIBUS") (pin "CR1") (pinfunction "1_CR1") (pintype "bidirectional"))
    )
    (net (code "66") (name "LAST_WORD_PL") (class "Default")
      (node (ref "E46") (pin "10") (pinfunction "I1_10") (pintype "input"))
      (node (ref "J") (pin "N2") (pinfunction "P_N2") (pintype "passive"))
    )
    (net (code "67") (name "LD_CMD_REG") (class "Default")
      (node (ref "E34") (pin "6") (pinfunction "I1_6") (pintype "input"))
      (node (ref "J") (pin "P1") (pinfunction "P_P1") (pintype "passive"))
    )
    (net (code "68") (name "LD_DB4") (class "Default")
      (node (ref "E11") (pin "8") (pinfunction "O_8") (pintype "output"))
      (node (ref "E17") (pin "8") (pinfunction "CK2_8") (pintype "input"))
      (node (ref "E24") (pin "8") (pinfunction "CK2_8") (pintype "input"))
      (node (ref "E9") (pin "8") (pinfunction "CK2_8") (pintype "input"))
    )
    (net (code "69") (name "LD_DB_AC") (class "Default")
      (node (ref "E21") (pin "8") (pinfunction "O_8") (pintype "output"))
      (node (ref "E26") (pin "2") (pinfunction "I5_2") (pintype "input"))
    )
    (net (code "70") (name "LD_DISK_ADDRS") (class "Default")
      (node (ref "E27") (pin "9") (pinfunction "I_9") (pintype "input"))
      (node (ref "E52") (pin "3") (pinfunction "CLK_3") (pintype "input"))
      (node (ref "J") (pin "B2") (pinfunction "P_B2") (pintype "passive"))
    )
    (net (code "71") (name "LD_RD_BUFFER") (class "Default")
      (node (ref "E13") (pin "2") (pinfunction "I0_2") (pintype "input"))
      (node (ref "E19") (pin "13") (pinfunction "O_13") (pintype "output"))
      (node (ref "E3") (pin "8") (pinfunction "CK2_8") (pintype "input"))
      (node (ref "E32") (pin "8") (pinfunction "CK2_8") (pintype "input"))
      (node (ref "E5") (pin "8") (pinfunction "CK2_8") (pintype "input"))
    )
    (net (code "72") (name "LO_MAIN_DATA") (class "Default")
      (node (ref "E9") (pin "1") (pinfunction "SER_1") (pintype "input"))
      (node (ref "H") (pin "V2") (pinfunction "P_V2") (pintype "passive"))
    )
    (net (code "73") (name "MAIN") (class "Default")
      (node (ref "E38") (pin "1") (pinfunction "CLR_1") (pintype "input"))
      (node (ref "E46") (pin "9") (pinfunction "I0_9") (pintype "input"))
      (node (ref "H") (pin "A2") (pinfunction "P_A2") (pintype "passive"))
    )
    (net (code "74") (name "MAIN_PL") (class "Default")
      (node (ref "E20") (pin "9") (pinfunction "I0_9") (pintype "input"))
      (node (ref "H") (pin "T1") (pinfunction "P_T1") (pintype "passive"))
    )
    (net (code "75") (name "MD_RD_BUFF") (class "Default")
      (node (ref "E27") (pin "4") (pinfunction "O_4") (pintype "output"))
      (node (ref "E3") (pin "6") (pinfunction "MOD_6") (pintype "input"))
      (node (ref "E32") (pin "6") (pinfunction "MOD_6") (pintype "input"))
      (node (ref "E5") (pin "6") (pinfunction "MOD_6") (pintype "input"))
      (node (ref "E51") (pin "2") (pinfunction "I0_2") (pintype "input"))
    )
    (net (code "76") (name "Net-(E1A-I0)") (class "Default")
      (node (ref "E1") (pin "4") (pinfunction "I0_4") (pintype "input"))
      (node (ref "W1W4") (pin "2") (pinfunction "2_2") (pintype "passive"))
    )
    (net (code "77") (name "Net-(E1A-I1)") (class "Default")
      (node (ref "E1") (pin "5") (pinfunction "I1_5") (pintype "input"))
      (node (ref "W2W5") (pin "2") (pinfunction "2_2") (pintype "passive"))
    )
    (net (code "78") (name "Net-(E1A-I2)") (class "Default")
      (node (ref "E1") (pin "6") (pinfunction "I2_6") (pintype "input"))
      (node (ref "W3W6") (pin "2") (pinfunction "2_2") (pintype "passive"))
    )
    (net (code "79") (name "Net-(E1A-O)") (class "Default")
      (node (ref "E1") (pin "3") (pinfunction "O_3") (pintype "output"))
      (node (ref "R18") (pin "1") (pinfunction "1_1") (pintype "passive"))
    )
    (net (code "80") (name "Net-(E3A-QA)") (class "Default")
      (node (ref "E3") (pin "13") (pinfunction "QA_13") (pintype "output"))
      (node (ref "E4") (pin "3") (pinfunction "D1_3") (pintype "input"))
    )
    (net (code "81") (name "Net-(E3A-QB)") (class "Default")
      (node (ref "E3") (pin "12") (pinfunction "QB_12") (pintype "output"))
      (node (ref "E4") (pin "4") (pinfunction "D2_4") (pintype "input"))
    )
    (net (code "82") (name "Net-(E3A-QC)") (class "Default")
      (node (ref "E3") (pin "11") (pinfunction "QC_11") (pintype "output"))
      (node (ref "E4") (pin "6") (pinfunction "D3_6") (pintype "input"))
    )
    (net (code "83") (name "Net-(E3A-QD)") (class "Default")
      (node (ref "E3") (pin "10") (pinfunction "QD_10") (pintype "output"))
      (node (ref "E4") (pin "11") (pinfunction "D4_11") (pintype "input"))
      (node (ref "E5") (pin "1") (pinfunction "SER_1") (pintype "input"))
    )
    (net (code "84") (name "Net-(E4A-D5)") (class "Default")
      (node (ref "E4") (pin "13") (pinfunction "D5_13") (pintype "input"))
      (node (ref "E5") (pin "13") (pinfunction "QA_13") (pintype "output"))
    )
    (net (code "85") (name "Net-(E4A-D6)") (class "Default")
      (node (ref "E4") (pin "14") (pinfunction "D6_14") (pintype "input"))
      (node (ref "E5") (pin "12") (pinfunction "QB_12") (pintype "output"))
    )
    (net (code "86") (name "Net-(E6A-O)") (class "Default")
      (node (ref "E6") (pin "8") (pinfunction "O_8") (pintype "output"))
      (node (ref "E7") (pin "1") (pinfunction "A_1") (pintype "input"))
    )
    (net (code "87") (name "Net-(E7A-C)") (class "Default")
      (node (ref "C48") (pin "2") (pinfunction "2_2") (pintype "passive"))
      (node (ref "E7") (pin "14") (pinfunction "C_14") (pintype "input"))
    )
    (net (code "88") (name "Net-(E7A-R{slash}C)") (class "Default")
      (node (ref "C48") (pin "1") (pinfunction "1_1") (pintype "passive"))
      (node (ref "E7") (pin "15") (pinfunction "R/C_15") (pintype "input"))
      (node (ref "R7") (pin "1") (pinfunction "1_1") (pintype "passive"))
    )
    (net (code "89") (name "Net-(E7B-C)") (class "Default")
      (node (ref "C47") (pin "2") (pinfunction "2_2") (pintype "passive"))
      (node (ref "E7") (pin "6") (pinfunction "C_6") (pintype "input"))
    )
    (net (code "90") (name "Net-(E7B-R{slash}C)") (class "Default")
      (node (ref "C47") (pin "1") (pinfunction "1_1") (pintype "passive"))
      (node (ref "E7") (pin "7") (pinfunction "R/C_7") (pintype "input"))
      (node (ref "R6") (pin "1") (pinfunction "1_1") (pintype "passive"))
    )
    (net (code "91") (name "Net-(E10A-D1)") (class "Default")
      (node (ref "E10") (pin "3") (pinfunction "D1_3") (pintype "input"))
      (node (ref "E4") (pin "2") (pinfunction "Q1_2") (pintype "output"))
    )
    (net (code "92") (name "Net-(E10A-D2)") (class "Default")
      (node (ref "E10") (pin "4") (pinfunction "D2_4") (pintype "input"))
      (node (ref "E4") (pin "5") (pinfunction "Q2_5") (pintype "output"))
    )
    (net (code "93") (name "Net-(E10A-D3)") (class "Default")
      (node (ref "E10") (pin "6") (pinfunction "D3_6") (pintype "input"))
      (node (ref "E4") (pin "7") (pinfunction "Q3_7") (pintype "output"))
    )
    (net (code "94") (name "Net-(E10A-D4)") (class "Default")
      (node (ref "E10") (pin "11") (pinfunction "D4_11") (pintype "input"))
      (node (ref "E4") (pin "10") (pinfunction "Q4_10") (pintype "output"))
    )
    (net (code "95") (name "Net-(E10A-D5)") (class "Default")
      (node (ref "E10") (pin "13") (pinfunction "D5_13") (pintype "input"))
      (node (ref "E4") (pin "12") (pinfunction "Q5_12") (pintype "output"))
    )
    (net (code "96") (name "Net-(E10A-D6)") (class "Default")
      (node (ref "E10") (pin "14") (pinfunction "D6_14") (pintype "input"))
      (node (ref "E4") (pin "15") (pinfunction "Q6_15") (pintype "output"))
    )
    (net (code "97") (name "Net-(E10A-Q1)") (class "Default")
      (node (ref "E10") (pin "2") (pinfunction "Q1_2") (pintype "output"))
      (node (ref "E9") (pin "2") (pinfunction "A_2") (pintype "input"))
    )
    (net (code "98") (name "Net-(E10A-Q2)") (class "Default")
      (node (ref "E10") (pin "5") (pinfunction "Q2_5") (pintype "output"))
      (node (ref "E9") (pin "3") (pinfunction "B_3") (pintype "input"))
    )
    (net (code "99") (name "Net-(E10A-Q3)") (class "Default")
      (node (ref "E10") (pin "7") (pinfunction "Q3_7") (pintype "output"))
      (node (ref "E9") (pin "4") (pinfunction "C_4") (pintype "input"))
    )
    (net (code "100") (name "Net-(E10A-Q4)") (class "Default")
      (node (ref "E10") (pin "10") (pinfunction "Q4_10") (pintype "output"))
      (node (ref "E9") (pin "5") (pinfunction "D_5") (pintype "input"))
    )
    (net (code "101") (name "Net-(E10A-Q5)") (class "Default")
      (node (ref "E10") (pin "12") (pinfunction "Q5_12") (pintype "output"))
      (node (ref "E17") (pin "2") (pinfunction "A_2") (pintype "input"))
    )
    (net (code "102") (name "Net-(E10A-Q6)") (class "Default")
      (node (ref "E10") (pin "15") (pinfunction "Q6_15") (pintype "output"))
      (node (ref "E17") (pin "3") (pinfunction "B_3") (pintype "input"))
    )
    (net (code "103") (name "Net-(E11A-O)") (class "Default")
      (node (ref "E11") (pin "3") (pinfunction "O_3") (pintype "output"))
      (node (ref "E13") (pin "3") (pinfunction "I1_3") (pintype "input"))
    )
    (net (code "104") (name "Net-(E11B-O)") (class "Default")
      (node (ref "E11") (pin "6") (pinfunction "O_6") (pintype "output"))
      (node (ref "E19") (pin "9") (pinfunction "I1_9") (pintype "input"))
    )
    (net (code "105") (name "Net-(E12A-CL)") (class "Default")
      (node (ref "E12") (pin "2") (pinfunction "CL_2") (pintype "input"))
      (node (ref "E19") (pin "10") (pinfunction "O_10") (pintype "output"))
    )
    (net (code "106") (name "Net-(E12A-CLK)") (class "Default")
      (node (ref "E12") (pin "1") (pinfunction "CLK_1") (pintype "input"))
      (node (ref "E27") (pin "6") (pinfunction "O_6") (pintype "output"))
    )
    (net (code "107") (name "Net-(E12A-J)") (class "Default")
      (node (ref "E12") (pin "14") (pinfunction "J_14") (pintype "input"))
      (node (ref "E47") (pin "12") (pinfunction "O_12") (pintype "output"))
    )
    (net (code "108") (name "Net-(E13A-O)") (class "Default")
      (node (ref "E13") (pin "1") (pinfunction "O_1") (pintype "output"))
      (node (ref "E27") (pin "5") (pinfunction "I_5") (pintype "input"))
    )
    (net (code "109") (name "Net-(E13B-I0)") (class "Default")
      (node (ref "C49") (pin "1") (pinfunction "1_1") (pintype "passive"))
      (node (ref "E13") (pin "5") (pinfunction "I0_5") (pintype "input"))
      (node (ref "R14") (pin "2") (pinfunction "2_2") (pintype "passive"))
    )
    (net (code "110") (name "Net-(E14B-PRE)") (class "Default")
      (node (ref "E14") (pin "7") (pinfunction "PRE_7") (pintype "input"))
      (node (ref "E20") (pin "8") (pinfunction "O_8") (pintype "output"))
    )
    (net (code "111") (name "Net-(E17A-C)") (class "Default")
      (node (ref "E17") (pin "4") (pinfunction "C_4") (pintype "input"))
      (node (ref "E18") (pin "2") (pinfunction "Q1_2") (pintype "output"))
    )
    (net (code "112") (name "Net-(E17A-D)") (class "Default")
      (node (ref "E17") (pin "5") (pinfunction "D_5") (pintype "input"))
      (node (ref "E18") (pin "5") (pinfunction "Q2_5") (pintype "output"))
    )
    (net (code "113") (name "Net-(E17A-MOD)") (class "Default")
      (node (ref "C56") (pin "1") (pinfunction "1_1") (pintype "passive"))
      (node (ref "E17") (pin "6") (pinfunction "MOD_6") (pintype "input"))
      (node (ref "E24") (pin "6") (pinfunction "MOD_6") (pintype "input"))
      (node (ref "E9") (pin "6") (pinfunction "MOD_6") (pintype "input"))
      (node (ref "R15") (pin "2") (pinfunction "2_2") (pintype "passive"))
    )
    (net (code "114") (name "Net-(E18A-D1)") (class "Default")
      (node (ref "E18") (pin "3") (pinfunction "D1_3") (pintype "input"))
      (node (ref "E25") (pin "2") (pinfunction "Q1_2") (pintype "output"))
    )
    (net (code "115") (name "Net-(E18A-D2)") (class "Default")
      (node (ref "E18") (pin "4") (pinfunction "D2_4") (pintype "input"))
      (node (ref "E25") (pin "5") (pinfunction "Q2_5") (pintype "output"))
    )
    (net (code "116") (name "Net-(E18A-D3)") (class "Default")
      (node (ref "E18") (pin "6") (pinfunction "D3_6") (pintype "input"))
      (node (ref "E25") (pin "7") (pinfunction "Q3_7") (pintype "output"))
    )
    (net (code "117") (name "Net-(E18A-D4)") (class "Default")
      (node (ref "E18") (pin "11") (pinfunction "D4_11") (pintype "input"))
      (node (ref "E25") (pin "10") (pinfunction "Q4_10") (pintype "output"))
    )
    (net (code "118") (name "Net-(E18A-D5)") (class "Default")
      (node (ref "E18") (pin "13") (pinfunction "D5_13") (pintype "input"))
      (node (ref "E25") (pin "12") (pinfunction "Q5_12") (pintype "output"))
    )
    (net (code "119") (name "Net-(E18A-D6)") (class "Default")
      (node (ref "E18") (pin "14") (pinfunction "D6_14") (pintype "input"))
      (node (ref "E25") (pin "15") (pinfunction "Q6_15") (pintype "output"))
    )
    (net (code "120") (name "Net-(E18A-Q3)") (class "Default")
      (node (ref "E18") (pin "7") (pinfunction "Q3_7") (pintype "output"))
      (node (ref "E24") (pin "2") (pinfunction "A_2") (pintype "input"))
    )
    (net (code "121") (name "Net-(E18A-Q4)") (class "Default")
      (node (ref "E18") (pin "10") (pinfunction "Q4_10") (pintype "output"))
      (node (ref "E24") (pin "3") (pinfunction "B_3") (pintype "input"))
    )
    (net (code "122") (name "Net-(E18A-Q5)") (class "Default")
      (node (ref "E18") (pin "12") (pinfunction "Q5_12") (pintype "output"))
      (node (ref "E24") (pin "4") (pinfunction "C_4") (pintype "input"))
    )
    (net (code "123") (name "Net-(E18A-Q6)") (class "Default")
      (node (ref "E18") (pin "15") (pinfunction "Q6_15") (pintype "output"))
      (node (ref "E24") (pin "5") (pinfunction "D_5") (pintype "input"))
    )
    (net (code "124") (name "Net-(E25A-D1)") (class "Default")
      (node (ref "E25") (pin "3") (pinfunction "D1_3") (pintype "input"))
      (node (ref "E5") (pin "11") (pinfunction "QC_11") (pintype "output"))
    )
    (net (code "125") (name "Net-(E25A-D2)") (class "Default")
      (node (ref "E25") (pin "4") (pinfunction "D2_4") (pintype "input"))
      (node (ref "E32") (pin "1") (pinfunction "SER_1") (pintype "input"))
      (node (ref "E5") (pin "10") (pinfunction "QD_10") (pintype "output"))
    )
    (net (code "126") (name "Net-(E25A-D3)") (class "Default")
      (node (ref "E25") (pin "6") (pinfunction "D3_6") (pintype "input"))
      (node (ref "E32") (pin "13") (pinfunction "QA_13") (pintype "output"))
    )
    (net (code "127") (name "Net-(E25A-D4)") (class "Default")
      (node (ref "E25") (pin "11") (pinfunction "D4_11") (pintype "input"))
      (node (ref "E32") (pin "12") (pinfunction "QB_12") (pintype "output"))
    )
    (net (code "128") (name "Net-(E25A-D5)") (class "Default")
      (node (ref "E25") (pin "13") (pinfunction "D5_13") (pintype "input"))
      (node (ref "E32") (pin "11") (pinfunction "QC_11") (pintype "output"))
    )
    (net (code "129") (name "Net-(E25A-D6)") (class "Default")
      (node (ref "E25") (pin "14") (pinfunction "D6_14") (pintype "input"))
      (node (ref "E32") (pin "10") (pinfunction "QD_10") (pintype "output"))
    )
    (net (code "130") (name "Net-(E27A-O)") (class "Default")
      (node (ref "E27") (pin "2") (pinfunction "O_2") (pintype "output"))
      (node (ref "R10") (pin "1") (pinfunction "1_1") (pintype "passive"))
    )
    (net (code "131") (name "Net-(E27D-O)") (class "Default")
      (node (ref "E27") (pin "8") (pinfunction "O_8") (pintype "output"))
      (node (ref "E54") (pin "5") (pinfunction "I1_5") (pintype "input"))
    )
    (net (code "132") (name "Net-(E27F-O)") (class "Default")
      (node (ref "E27") (pin "12") (pinfunction "O_12") (pintype "output"))
      (node (ref "R8") (pin "1") (pinfunction "1_1") (pintype "passive"))
    )
    (net (code "133") (name "Net-(E28A-O)") (class "Default")
      (node (ref "E28") (pin "1") (pinfunction "O_1") (pintype "output"))
      (node (ref "E28") (pin "5") (pinfunction "I0_5") (pintype "input"))
    )
    (net (code "134") (name "Net-(E28B-I1)") (class "Default")
      (node (ref "E28") (pin "10") (pinfunction "O_10") (pintype "output"))
      (node (ref "E28") (pin "6") (pinfunction "I1_6") (pintype "input"))
    )
    (net (code "135") (name "Net-(E28B-O)") (class "Default")
      (node (ref "E28") (pin "11") (pinfunction "I0_11") (pintype "input"))
      (node (ref "E28") (pin "4") (pinfunction "O_4") (pintype "output"))
    )
    (net (code "136") (name "Net-(E28D-O)") (class "Default")
      (node (ref "E28") (pin "13") (pinfunction "O_13") (pintype "output"))
      (node (ref "E34") (pin "12") (pinfunction "I1_12") (pintype "input"))
    )
    (net (code "137") (name "Net-(E29A-A1)") (class "Default")
      (node (ref "E29") (pin "6") (pinfunction "A1_6") (pintype "input"))
      (node (ref "E44") (pin "8") (pinfunction "O_8") (pintype "output"))
    )
    (net (code "138") (name "Net-(E29A-B1)") (class "Default")
      (node (ref "E29") (pin "5") (pinfunction "B1_5") (pintype "input"))
      (node (ref "E40") (pin "8") (pinfunction "O_8") (pintype "output"))
    )
    (net (code "139") (name "Net-(E30C-O)") (class "Default")
      (node (ref "E30") (pin "14") (pinfunction "O_14") (pintype "output"))
      (node (ref "E48") (pin "1") (pinfunction "I0_1") (pintype "input"))
      (node (ref "E53") (pin "9") (pinfunction "I1_9") (pintype "input"))
    )
    (net (code "140") (name "Net-(E33C-I0)") (class "Default")
      (node (ref "E33") (pin "9") (pinfunction "I0_9") (pintype "input"))
      (node (ref "E35") (pin "2") (pinfunction "O_2") (pintype "output"))
    )
    (net (code "141") (name "Net-(E33C-I1)") (class "Default")
      (node (ref "E33") (pin "10") (pinfunction "I1_10") (pintype "input"))
      (node (ref "E41") (pin "6") (pinfunction "O_6") (pintype "output"))
    )
    (net (code "142") (name "Net-(E34B-O)") (class "Default")
      (node (ref "E34") (pin "4") (pinfunction "O_4") (pintype "output"))
      (node (ref "E48") (pin "4") (pinfunction "I0_4") (pintype "input"))
    )
    (net (code "143") (name "Net-(E34D-O)") (class "Default")
      (node (ref "E34") (pin "13") (pinfunction "O_13") (pintype "output"))
      (node (ref "E38") (pin "13") (pinfunction "CLR_13") (pintype "input"))
    )
    (net (code "144") (name "Net-(E35A-O)") (class "Default")
      (node (ref "E35") (pin "3") (pinfunction "O_3") (pintype "output"))
      (node (ref "E35") (pin "6") (pinfunction "I0_6") (pintype "input"))
    )
    (net (code "145") (name "Net-(E35D-O)") (class "Default")
      (node (ref "E35") (pin "13") (pinfunction "O_13") (pintype "output"))
      (node (ref "E38") (pin "2") (pinfunction "D_2") (pintype "input"))
    )
    (net (code "146") (name "Net-(E36A-I0)") (class "Default")
      (node (ref "E36") (pin "2") (pinfunction "I0_2") (pintype "input"))
      (node (ref "E36") (pin "5") (pinfunction "I0_5") (pintype "input"))
      (node (ref "E54") (pin "3") (pinfunction "O_3") (pintype "output"))
    )
    (net (code "147") (name "Net-(E39A-PRE)") (class "Default")
      (node (ref "E39") (pin "4") (pinfunction "PRE_4") (pintype "input"))
      (node (ref "E46") (pin "6") (pinfunction "O_6") (pintype "output"))
    )
    (net (code "148") (name "Net-(E39B-CLK)") (class "Default")
      (node (ref "E39") (pin "11") (pinfunction "CLK_11") (pintype "input"))
      (node (ref "E46") (pin "11") (pinfunction "O_11") (pintype "output"))
    )
    (net (code "149") (name "Net-(E39B-CLR)") (class "Default")
      (node (ref "E39") (pin "13") (pinfunction "CLR_13") (pintype "input"))
      (node (ref "E46") (pin "8") (pinfunction "O_8") (pintype "output"))
    )
    (net (code "150") (name "Net-(E40B-I1)") (class "Default")
      (node (ref "DL1") (pin "OUT") (pinfunction "OUT_OUT") (pintype "bidirectional"))
      (node (ref "E40") (pin "5") (pinfunction "I1_5") (pintype "input"))
      (node (ref "R16") (pin "1") (pinfunction "1_1") (pintype "passive"))
    )
    (net (code "151") (name "Net-(E40B-O)") (class "Default")
      (node (ref "E40") (pin "6") (pinfunction "O_6") (pintype "output"))
      (node (ref "E46") (pin "2") (pinfunction "I1_2") (pintype "input"))
    )
    (net (code "152") (name "Net-(E40D-I1)") (class "Default")
      (node (ref "C50") (pin "1") (pinfunction "1_1") (pintype "passive"))
      (node (ref "E40") (pin "13") (pinfunction "I1_13") (pintype "input"))
      (node (ref "R8") (pin "2") (pinfunction "2_2") (pintype "passive"))
    )
    (net (code "153") (name "Net-(E41D-I3)") (class "Default")
      (node (ref "E41") (pin "13") (pinfunction "I3_13") (pintype "input"))
      (node (ref "E45") (pin "3") (pinfunction "O_3") (pintype "output"))
    )
    (net (code "154") (name "Net-(E41D-O)") (class "Default")
      (node (ref "E41") (pin "8") (pinfunction "O_8") (pintype "output"))
      (node (ref "E48") (pin "12") (pinfunction "I0_12") (pintype "input"))
    )
    (net (code "155") (name "Net-(E45B-O)") (class "Default")
      (node (ref "E45") (pin "6") (pinfunction "O_6") (pintype "output"))
      (node (ref "R5") (pin "1") (pinfunction "1_1") (pintype "passive"))
    )
    (net (code "156") (name "Net-(E45C-O)") (class "Default")
      (node (ref "E45") (pin "8") (pinfunction "O_8") (pintype "output"))
      (node (ref "E48") (pin "5") (pinfunction "I1_5") (pintype "input"))
    )
    (net (code "157") (name "Net-(E45D-I1)") (class "Default")
      (node (ref "C52") (pin "1") (pinfunction "1_1") (pintype "passive"))
      (node (ref "E45") (pin "13") (pinfunction "I1_13") (pintype "input"))
      (node (ref "R5") (pin "2") (pinfunction "2_2") (pintype "passive"))
    )
    (net (code "158") (name "Net-(E46A-I0)") (class "Default")
      (node (ref "C51") (pin "1") (pinfunction "1_1") (pintype "passive"))
      (node (ref "E46") (pin "1") (pinfunction "I0_1") (pintype "input"))
      (node (ref "R10") (pin "2") (pinfunction "2_2") (pintype "passive"))
    )
    (net (code "159") (name "Net-(E46D-I0)") (class "Default")
      (node (ref "E46") (pin "12") (pinfunction "I0_12") (pintype "input"))
      (node (ref "E47") (pin "6") (pinfunction "O_6") (pintype "output"))
    )
    (net (code "160") (name "Net-(E47C-I1)") (class "Default")
      (node (ref "E47") (pin "10") (pinfunction "I1_10") (pintype "input"))
      (node (ref "E53") (pin "1") (pinfunction "O_1") (pintype "output"))
    )
    (net (code "161") (name "Net-(E47C-I2)") (class "Default")
      (node (ref "E47") (pin "11") (pinfunction "I2_11") (pintype "input"))
      (node (ref "E53") (pin "4") (pinfunction "O_4") (pintype "output"))
    )
    (net (code "162") (name "Net-(E47C-O)") (class "Default")
      (node (ref "E47") (pin "8") (pinfunction "O_8") (pintype "output"))
      (node (ref "E53") (pin "11") (pinfunction "I0_11") (pintype "input"))
      (node (ref "E53") (pin "8") (pinfunction "I0_8") (pintype "input"))
    )
    (net (code "163") (name "Net-(E48A-O)") (class "Default")
      (node (ref "E48") (pin "3") (pinfunction "O_3") (pintype "output"))
      (node (ref "E53") (pin "12") (pinfunction "I1_12") (pintype "input"))
    )
    (net (code "164") (name "Net-(E48C-O)") (class "Default")
      (node (ref "E48") (pin "13") (pinfunction "I1_13") (pintype "input"))
      (node (ref "E48") (pin "8") (pinfunction "O_8") (pintype "output"))
    )
    (net (code "165") (name "Net-(E51D-O)") (class "Default")
      (node (ref "E51") (pin "13") (pinfunction "O_13") (pintype "output"))
      (node (ref "E52") (pin "2") (pinfunction "D_2") (pintype "input"))
    )
    (net (code "166") (name "Net-(E52B-CLK)") (class "Default")
      (node (ref "E52") (pin "11") (pinfunction "CLK_11") (pintype "input"))
      (node (ref "E54") (pin "8") (pinfunction "O_8") (pintype "output"))
    )
    (net (code "167") (name "POWER_OK") (class "Default")
      (node (ref "E35") (pin "4") (pinfunction "I0_4") (pintype "input"))
      (node (ref "OMNIBUS") (pin "BV2") (pinfunction "1_BV2") (pintype "bidirectional"))
    )
    (net (code "168") (name "RDY_S{slash}R{slash}W_SLO") (class "Default")
      (node (ref "E47") (pin "3") (pinfunction "I0_3") (pintype "input"))
      (node (ref "J") (pin "L1") (pinfunction "P_L1") (pintype "passive"))
    )
    (net (code "169") (name "RK_DATA0") (class "Default")
      (node (ref "E16") (pin "5") (pinfunction "I_5") (pintype "input"))
      (node (ref "E9") (pin "13") (pinfunction "QA_13") (pintype "output"))
    )
    (net (code "170") (name "RK_DATA1") (class "Default")
      (node (ref "E16") (pin "3") (pinfunction "I_3") (pintype "input"))
      (node (ref "E9") (pin "12") (pinfunction "QB_12") (pintype "output"))
    )
    (net (code "171") (name "RK_DATA2") (class "Default")
      (node (ref "E16") (pin "11") (pinfunction "I_11") (pintype "input"))
      (node (ref "E9") (pin "11") (pinfunction "QC_11") (pintype "output"))
    )
    (net (code "172") (name "RK_DATA3") (class "Default")
      (node (ref "E16") (pin "9") (pinfunction "I_9") (pintype "input"))
      (node (ref "E17") (pin "1") (pinfunction "SER_1") (pintype "input"))
      (node (ref "E9") (pin "10") (pinfunction "QD_10") (pintype "output"))
    )
    (net (code "173") (name "RK_DATA4") (class "Default")
      (node (ref "E17") (pin "13") (pinfunction "QA_13") (pintype "output"))
      (node (ref "E23") (pin "9") (pinfunction "I_9") (pintype "input"))
    )
    (net (code "174") (name "RK_DATA5") (class "Default")
      (node (ref "E16") (pin "13") (pinfunction "I_13") (pintype "input"))
      (node (ref "E17") (pin "12") (pinfunction "QB_12") (pintype "output"))
    )
    (net (code "175") (name "RK_DATA6") (class "Default")
      (node (ref "E16") (pin "1") (pinfunction "I_1") (pintype "input"))
      (node (ref "E17") (pin "11") (pinfunction "QC_11") (pintype "output"))
    )
    (net (code "176") (name "RK_DATA7") (class "Default")
      (node (ref "E17") (pin "10") (pinfunction "QD_10") (pintype "output"))
      (node (ref "E23") (pin "11") (pinfunction "I_11") (pintype "input"))
      (node (ref "E24") (pin "1") (pinfunction "SER_1") (pintype "input"))
    )
    (net (code "177") (name "RK_DATA8") (class "Default")
      (node (ref "E23") (pin "1") (pinfunction "I_1") (pintype "input"))
      (node (ref "E24") (pin "13") (pinfunction "QA_13") (pintype "output"))
    )
    (net (code "178") (name "RK_DATA9") (class "Default")
      (node (ref "E23") (pin "5") (pinfunction "I_5") (pintype "input"))
      (node (ref "E24") (pin "12") (pinfunction "QB_12") (pintype "output"))
    )
    (net (code "179") (name "RK_DATA10") (class "Default")
      (node (ref "E23") (pin "3") (pinfunction "I_3") (pintype "input"))
      (node (ref "E24") (pin "11") (pinfunction "QC_11") (pintype "output"))
    )
    (net (code "180") (name "RK_DATA11") (class "Default")
      (node (ref "E23") (pin "13") (pinfunction "I_13") (pintype "input"))
      (node (ref "E24") (pin "10") (pinfunction "QD_10") (pintype "output"))
      (node (ref "H") (pin "F1") (pinfunction "P_F1") (pintype "passive"))
    )
    (net (code "181") (name "SEEK_FAIL") (class "Default")
      (node (ref "E8") (pin "15") (pinfunction "A3_15") (pintype "input"))
      (node (ref "H") (pin "U2") (pinfunction "P_U2") (pintype "passive"))
    )
    (net (code "182") (name "SET_BUSY_ER") (class "Default")
      (node (ref "E48") (pin "11") (pinfunction "O_11") (pintype "output"))
      (node (ref "E50") (pin "2") (pinfunction "A_2") (pintype "input"))
    )
    (net (code "183") (name "SET_CRC_ER") (class "Default")
      (node (ref "E50") (pin "3") (pinfunction "B_3") (pintype "input"))
      (node (ref "E51") (pin "4") (pinfunction "O_4") (pintype "output"))
    )
    (net (code "184") (name "SET_CYL_ADDRS_ER") (class "Default")
      (node (ref "E50") (pin "7") (pinfunction "E_7") (pintype "input"))
      (node (ref "E51") (pin "10") (pinfunction "O_10") (pintype "output"))
    )
    (net (code "185") (name "SET_STATUS_ER") (class "Default")
      (node (ref "E45") (pin "11") (pinfunction "O_11") (pintype "output"))
      (node (ref "E50") (pin "6") (pinfunction "D_6") (pintype "input"))
    )
    (net (code "186") (name "SET_TIME_OUT_ER") (class "Default")
      (node (ref "E43") (pin "7") (pinfunction "QD_7") (pintype "output"))
      (node (ref "E50") (pin "4") (pinfunction "C_4") (pintype "input"))
    )
    (net (code "187") (name "SHORT_TP3") (class "Default")
      (node (ref "E40") (pin "11") (pinfunction "O_11") (pintype "output"))
      (node (ref "E48") (pin "9") (pinfunction "I0_9") (pintype "input"))
    )
    (net (code "188") (name "TEST_CLK") (class "Default")
      (node (ref "E34") (pin "8") (pinfunction "I0_8") (pintype "input"))
      (node (ref "E7") (pin "5") (pinfunction "Q_5") (pintype "output"))
    )
    (net (code "189") (name "TIME_OUT_ER") (class "Default")
      (node (ref "E22") (pin "10") (pinfunction "A2_10") (pintype "input"))
      (node (ref "E50") (pin "13") (pinfunction "QC_13") (pintype "output"))
      (node (ref "E53") (pin "6") (pinfunction "I1_6") (pintype "input"))
    )
    (net (code "190") (name "TP1") (class "Default")
      (node (ref "E30") (pin "11") (pinfunction "I0_11") (pintype "input"))
      (node (ref "OMNIBUS") (pin "CD2") (pinfunction "1_CD2") (pintype "bidirectional"))
    )
    (net (code "191") (name "TP2") (class "Default")
      (node (ref "E30") (pin "7") (pinfunction "I1_7") (pintype "input"))
      (node (ref "OMNIBUS") (pin "CE2") (pinfunction "1_CE2") (pintype "bidirectional"))
    )
    (net (code "192") (name "TP3") (class "Default")
      (node (ref "E30") (pin "4") (pinfunction "I0_4") (pintype "input"))
      (node (ref "OMNIBUS") (pin "CH2") (pinfunction "1_CH2") (pintype "bidirectional"))
    )
    (net (code "193") (name "VCC") (class "Default")
      (node (ref "C1") (pin "1") (pinfunction "1_1") (pintype "passive"))
      (node (ref "C10") (pin "1") (pinfunction "1_1") (pintype "passive"))
      (node (ref "C11") (pin "1") (pinfunction "1_1") (pintype "passive"))
      (node (ref "C12") (pin "1") (pinfunction "1_1") (pintype "passive"))
      (node (ref "C13") (pin "1") (pinfunction "1_1") (pintype "passive"))
      (node (ref "C14") (pin "1") (pinfunction "1_1") (pintype "passive"))
      (node (ref "C15") (pin "1") (pinfunction "1_1") (pintype "passive"))
      (node (ref "C16") (pin "1") (pinfunction "1_1") (pintype "passive"))
      (node (ref "C17") (pin "1") (pinfunction "1_1") (pintype "passive"))
      (node (ref "C18") (pin "1") (pinfunction "1_1") (pintype "passive"))
      (node (ref "C19") (pin "1") (pinfunction "1_1") (pintype "passive"))
      (node (ref "C2") (pin "1") (pinfunction "1_1") (pintype "passive"))
      (node (ref "C20") (pin "1") (pinfunction "1_1") (pintype "passive"))
      (node (ref "C21") (pin "1") (pinfunction "1_1") (pintype "passive"))
      (node (ref "C22") (pin "1") (pinfunction "1_1") (pintype "passive"))
      (node (ref "C23") (pin "1") (pinfunction "1_1") (pintype "passive"))
      (node (ref "C24") (pin "1") (pinfunction "1_1") (pintype "passive"))
      (node (ref "C25") (pin "1") (pinfunction "1_1") (pintype "passive"))
      (node (ref "C26") (pin "1") (pinfunction "1_1") (pintype "passive"))
      (node (ref "C27") (pin "1") (pinfunction "1_1") (pintype "passive"))
      (node (ref "C28") (pin "1") (pinfunction "1_1") (pintype "passive"))
      (node (ref "C29") (pin "1") (pinfunction "1_1") (pintype "passive"))
      (node (ref "C3") (pin "1") (pinfunction "1_1") (pintype "passive"))
      (node (ref "C30") (pin "1") (pinfunction "1_1") (pintype "passive"))
      (node (ref "C31") (pin "1") (pinfunction "1_1") (pintype "passive"))
      (node (ref "C32") (pin "1") (pinfunction "1_1") (pintype "passive"))
      (node (ref "C33") (pin "1") (pinfunction "1_1") (pintype "passive"))
      (node (ref "C34") (pin "1") (pinfunction "1_1") (pintype "passive"))
      (node (ref "C35") (pin "1") (pinfunction "1_1") (pintype "passive"))
      (node (ref "C36") (pin "1") (pinfunction "1_1") (pintype "passive"))
      (node (ref "C37") (pin "1") (pinfunction "1_1") (pintype "passive"))
      (node (ref "C38") (pin "1") (pinfunction "1_1") (pintype "passive"))
      (node (ref "C39") (pin "1") (pinfunction "1_1") (pintype "passive"))
      (node (ref "C4") (pin "1") (pinfunction "1_1") (pintype "passive"))
      (node (ref "C40") (pin "1") (pinfunction "1_1") (pintype "passive"))
      (node (ref "C41") (pin "1") (pinfunction "1_1") (pintype "passive"))
      (node (ref "C42") (pin "1") (pinfunction "1_1") (pintype "passive"))
      (node (ref "C43") (pin "1") (pinfunction "1_1") (pintype "passive"))
      (node (ref "C44") (pin "1") (pinfunction "1_1") (pintype "passive"))
      (node (ref "C45") (pin "1") (pinfunction "1_1") (pintype "passive"))
      (node (ref "C46") (pin "1") (pinfunction "1_1") (pintype "passive"))
      (node (ref "C5") (pin "1") (pinfunction "1_1") (pintype "passive"))
      (node (ref "C53") (pin "+") (pinfunction "+_+") (pintype "passive"))
      (node (ref "C54") (pin "+") (pinfunction "+_+") (pintype "passive"))
      (node (ref "C55") (pin "+") (pinfunction "+_+") (pintype "passive"))
      (node (ref "C6") (pin "1") (pinfunction "1_1") (pintype "passive"))
      (node (ref "C7") (pin "1") (pinfunction "1_1") (pintype "passive"))
      (node (ref "C8") (pin "1") (pinfunction "1_1") (pintype "passive"))
      (node (ref "C9") (pin "1") (pinfunction "1_1") (pintype "passive"))
      (node (ref "DL1") (pin "GND@1") (pinfunction "GND_GND@1") (pintype "power_in"))
      (node (ref "DL1") (pin "GND@2") (pinfunction "GND_GND@2") (pintype "power_in"))
      (node (ref "OMNIBUS") (pin "AA2") (pinfunction "1_AA2") (pintype "bidirectional"))
      (node (ref "OMNIBUS") (pin "BA2") (pinfunction "1_BA2") (pintype "bidirectional"))
      (node (ref "OMNIBUS") (pin "CA2") (pinfunction "1_CA2") (pintype "bidirectional"))
      (node (ref "R11") (pin "2") (pinfunction "2_2") (pintype "passive"))
      (node (ref "R12") (pin "2") (pinfunction "2_2") (pintype "passive"))
      (node (ref "R13") (pin "2") (pinfunction "2_2") (pintype "passive"))
      (node (ref "R16") (pin "2") (pinfunction "2_2") (pintype "passive"))
      (node (ref "R17") (pin "2") (pinfunction "2_2") (pintype "passive"))
      (node (ref "R2") (pin "2") (pinfunction "2_2") (pintype "passive"))
      (node (ref "R3") (pin "2") (pinfunction "2_2") (pintype "passive"))
      (node (ref "R6") (pin "2") (pinfunction "2_2") (pintype "passive"))
      (node (ref "R7") (pin "2") (pinfunction "2_2") (pintype "passive"))
      (node (ref "R9") (pin "2") (pinfunction "2_2") (pintype "passive"))
    )
    (net (code "194") (name "WRITE") (class "Default")
      (node (ref "E26") (pin "5") (pinfunction "I11_5") (pintype "input"))
      (node (ref "H") (pin "M2") (pinfunction "P_M2") (pintype "passive"))
    )
    (net (code "195") (name "WRT_BUFF_SHFT") (class "Default")
      (node (ref "E20") (pin "3") (pinfunction "O_3") (pintype "output"))
      (node (ref "E31") (pin "9") (pinfunction "I_9") (pintype "input"))
    )
    (net (code "196") (name "WRT_BUF_DATA") (class "Default")
      (node (ref "E21") (pin "12") (pinfunction "O_12") (pintype "output"))
      (node (ref "E54") (pin "10") (pinfunction "I1_10") (pintype "input"))
    )
    (net (code "197") (name "WRT_LOCK_ER") (class "Default")
      (node (ref "E22") (pin "15") (pinfunction "A3_15") (pintype "input"))
      (node (ref "E52") (pin "5") (pinfunction "Q_5") (pintype "output"))
      (node (ref "E53") (pin "5") (pinfunction "I0_5") (pintype "input"))
    )
    (net (code "198") (name "unconnected-(E6A-I9-Pad12)") (class "Default")
      (node (ref "E6") (pin "12") (pinfunction "I9_12") (pintype "passive"))
    )
    (net (code "199") (name "unconnected-(E6A-I10-Pad11)") (class "Default")
      (node (ref "E6") (pin "11") (pinfunction "I10_11") (pintype "passive"))
    )
    (net (code "200") (name "unconnected-(E7A-~{Q}-Pad4)") (class "Default")
      (node (ref "E7") (pin "4") (pinfunction "~{Q}_4") (pintype "output"))
    )
    (net (code "201") (name "unconnected-(E26A-I9-Pad12)") (class "Default")
      (node (ref "E26") (pin "12") (pinfunction "I9_12") (pintype "passive"))
    )
    (net (code "202") (name "unconnected-(E26A-I10-Pad11)") (class "Default")
      (node (ref "E26") (pin "11") (pinfunction "I10_11") (pintype "passive"))
    )
    (net (code "203") (name "unconnected-(E29A-A2-Pad10)") (class "Default")
      (node (ref "E29") (pin "10") (pinfunction "A2_10") (pintype "input"))
    )
    (net (code "204") (name "unconnected-(E29A-A3-Pad15)") (class "Default")
      (node (ref "E29") (pin "15") (pinfunction "A3_15") (pintype "input"))
    )
    (net (code "205") (name "unconnected-(E29A-B2-Pad11)") (class "Default")
      (node (ref "E29") (pin "11") (pinfunction "B2_11") (pintype "input"))
    )
    (net (code "206") (name "unconnected-(E29A-B3-Pad14)") (class "Default")
      (node (ref "E29") (pin "14") (pinfunction "B3_14") (pintype "input"))
    )
    (net (code "207") (name "unconnected-(E29A-F2-Pad12)") (class "Default")
      (node (ref "E29") (pin "12") (pinfunction "F2_12") (pintype "open_collector"))
    )
    (net (code "208") (name "unconnected-(E29A-F3-Pad13)") (class "Default")
      (node (ref "E29") (pin "13") (pinfunction "F3_13") (pintype "open_collector"))
    )
    (net (code "209") (name "unconnected-(E37A-0-Pad13)") (class "Default")
      (node (ref "E37") (pin "13") (pinfunction "0_13") (pintype "output"))
    )
    (net (code "210") (name "unconnected-(E37A-8-Pad6)") (class "Default")
      (node (ref "E37") (pin "6") (pinfunction "8_6") (pintype "output"))
    )
    (net (code "211") (name "unconnected-(E37A-9-Pad7)") (class "Default")
      (node (ref "E37") (pin "7") (pinfunction "9_7") (pintype "output"))
    )
    (net (code "212") (name "unconnected-(E38B-~{Q}-Pad8)") (class "Default")
      (node (ref "E38") (pin "8") (pinfunction "~{Q}_8") (pintype "output"))
    )
    (net (code "213") (name "unconnected-(E43A-A-Pad15)") (class "Default")
      (node (ref "E43") (pin "15") (pinfunction "A_15") (pintype "input"))
    )
    (net (code "214") (name "unconnected-(E43A-B-Pad1)") (class "Default")
      (node (ref "E43") (pin "1") (pinfunction "B_1") (pintype "input"))
    )
    (net (code "215") (name "unconnected-(E43A-BO-Pad13)") (class "Default")
      (node (ref "E43") (pin "13") (pinfunction "BO_13") (pintype "output"))
    )
    (net (code "216") (name "unconnected-(E43A-C-Pad10)") (class "Default")
      (node (ref "E43") (pin "10") (pinfunction "C_10") (pintype "input"))
    )
    (net (code "217") (name "unconnected-(E43A-CO-Pad12)") (class "Default")
      (node (ref "E43") (pin "12") (pinfunction "CO_12") (pintype "output"))
    )
    (net (code "218") (name "unconnected-(E43A-D-Pad9)") (class "Default")
      (node (ref "E43") (pin "9") (pinfunction "D_9") (pintype "input"))
    )
    (net (code "219") (name "unconnected-(E43A-QA-Pad3)") (class "Default")
      (node (ref "E43") (pin "3") (pinfunction "QA_3") (pintype "output"))
    )
    (net (code "220") (name "unconnected-(E43A-QB-Pad2)") (class "Default")
      (node (ref "E43") (pin "2") (pinfunction "QB_2") (pintype "output"))
    )
    (net (code "221") (name "unconnected-(E43A-QC-Pad6)") (class "Default")
      (node (ref "E43") (pin "6") (pinfunction "QC_6") (pintype "output"))
    )
    (net (code "222") (name "unconnected-(E50A-SER-Pad9)") (class "Default")
      (node (ref "E50") (pin "9") (pinfunction "SER_9") (pintype "input"))
    )
    (net (code "223") (name "unconnected-(E52B-~{Q}-Pad8)") (class "Default")
      (node (ref "E52") (pin "8") (pinfunction "~{Q}_8") (pintype "output"))
    )
    (net (code "224") (name "~{6RK1}") (class "Default")
      (node (ref "E31") (pin "11") (pinfunction "I_11") (pintype "input"))
      (node (ref "E37") (pin "12") (pinfunction "1_12") (pintype "output"))
    )
    (net (code "225") (name "~{6RK2}") (class "Default")
      (node (ref "DL1") (pin "IN") (pinfunction "IN_IN") (pintype "bidirectional"))
      (node (ref "E31") (pin "13") (pinfunction "I_13") (pintype "input"))
      (node (ref "E37") (pin "11") (pinfunction "2_11") (pintype "output"))
      (node (ref "E44") (pin "12") (pinfunction "I2_12") (pintype "input"))
      (node (ref "R17") (pin "1") (pinfunction "1_1") (pintype "passive"))
    )
    (net (code "226") (name "~{6RK3_OK}") (class "Default")
      (node (ref "E21") (pin "10") (pinfunction "O_10") (pintype "output"))
      (node (ref "H") (pin "S2") (pinfunction "P_S2") (pintype "passive"))
    )
    (net (code "227") (name "~{6RK3}") (class "Default")
      (node (ref "E19") (pin "5") (pinfunction "I0_5") (pintype "input"))
      (node (ref "E37") (pin "10") (pinfunction "3_10") (pintype "output"))
      (node (ref "E40") (pin "9") (pinfunction "I0_9") (pintype "input"))
      (node (ref "E41") (pin "9") (pinfunction "I0_9") (pintype "input"))
    )
    (net (code "228") (name "~{6RK4}") (class "Default")
      (node (ref "E37") (pin "9") (pinfunction "4_9") (pintype "output"))
      (node (ref "E41") (pin "12") (pinfunction "I2_12") (pintype "input"))
      (node (ref "E44") (pin "13") (pinfunction "I3_13") (pintype "input"))
      (node (ref "J") (pin "S2") (pinfunction "P_S2") (pintype "passive"))
    )
    (net (code "229") (name "~{6RK5}") (class "Default")
      (node (ref "E22") (pin "7") (pinfunction "S1_7") (pintype "input"))
      (node (ref "E29") (pin "2") (pinfunction "B0_2") (pintype "input"))
      (node (ref "E37") (pin "3") (pinfunction "5_3") (pintype "output"))
      (node (ref "E44") (pin "10") (pinfunction "I1_10") (pintype "input"))
      (node (ref "E49") (pin "7") (pinfunction "S1_7") (pintype "input"))
      (node (ref "E8") (pin "7") (pinfunction "S1_7") (pintype "input"))
    )
    (net (code "230") (name "~{6RK6}") (class "Default")
      (node (ref "E21") (pin "1") (pinfunction "I_1") (pintype "input"))
      (node (ref "E37") (pin "4") (pinfunction "6_4") (pintype "output"))
      (node (ref "E41") (pin "10") (pinfunction "I1_10") (pintype "input"))
      (node (ref "E44") (pin "9") (pinfunction "I0_9") (pintype "input"))
    )
    (net (code "231") (name "~{6RK7}") (class "Default")
      (node (ref "E19") (pin "2") (pinfunction "I0_2") (pintype "input"))
      (node (ref "E31") (pin "1") (pinfunction "I_1") (pintype "input"))
      (node (ref "E37") (pin "5") (pinfunction "7_5") (pintype "output"))
    )
    (net (code "232") (name "~{AC7}") (class "Default")
      (node (ref "E38") (pin "6") (pinfunction "~{Q}_6") (pintype "output"))
      (node (ref "H") (pin "B1") (pinfunction "P_B1") (pintype "passive"))
    )
    (net (code "233") (name "~{BDATA10}") (class "Default")
      (node (ref "E41") (pin "2") (pinfunction "I1_2") (pintype "input"))
      (node (ref "J") (pin "P2") (pinfunction "P_P2") (pintype "passive"))
    )
    (net (code "234") (name "~{BDATA11}") (class "Default")
      (node (ref "E44") (pin "2") (pinfunction "I1_2") (pintype "input"))
      (node (ref "E45") (pin "2") (pinfunction "I1_2") (pintype "input"))
      (node (ref "J") (pin "H1") (pinfunction "P_H1") (pintype "passive"))
    )
    (net (code "235") (name "~{BRK_DIR}") (class "Default")
      (node (ref "E20") (pin "5") (pinfunction "I1_5") (pintype "input"))
      (node (ref "H") (pin "P2") (pinfunction "P_P2") (pintype "passive"))
    )
    (net (code "236") (name "~{BTP3_OK}") (class "Default")
      (node (ref "E20") (pin "11") (pinfunction "O_11") (pintype "output"))
      (node (ref "E21") (pin "5") (pinfunction "I_5") (pintype "input"))
    )
    (net (code "237") (name "~{BTP3}") (class "Default")
      (node (ref "E19") (pin "12") (pinfunction "I1_12") (pintype "input"))
      (node (ref "E19") (pin "3") (pinfunction "I1_3") (pintype "input"))
      (node (ref "E21") (pin "4") (pinfunction "O_4") (pintype "output"))
      (node (ref "J") (pin "U1") (pinfunction "P_U1") (pintype "passive"))
    )
    (net (code "238") (name "~{C0}") (class "Default")
      (node (ref "E29") (pin "4") (pinfunction "F1_4") (pintype "open_collector"))
      (node (ref "OMNIBUS") (pin "CE1") (pinfunction "1_CE1") (pintype "bidirectional"))
    )
    (net (code "239") (name "~{C1}") (class "Default")
      (node (ref "E29") (pin "3") (pinfunction "F0_3") (pintype "open_collector"))
      (node (ref "OMNIBUS") (pin "CH1") (pinfunction "1_CH1") (pintype "bidirectional"))
    )
    (net (code "240") (name "~{CLR_ALL}") (class "Default")
      (node (ref "E12") (pin "6") (pinfunction "CL_6") (pintype "input"))
      (node (ref "E14") (pin "3") (pinfunction "CLR_3") (pintype "input"))
      (node (ref "E33") (pin "6") (pinfunction "O_6") (pintype "output"))
      (node (ref "J") (pin "U2") (pinfunction "P_U2") (pintype "passive"))
    )
    (net (code "241") (name "~{CLR_DRIVE_CMD}") (class "Default")
      (node (ref "E44") (pin "6") (pinfunction "O_6") (pintype "output"))
      (node (ref "E54") (pin "4") (pinfunction "I0_4") (pintype "input"))
      (node (ref "J") (pin "C2") (pinfunction "P_C2") (pintype "passive"))
    )
    (net (code "242") (name "~{CLR_STATUS}") (class "Default")
      (node (ref "E39") (pin "1") (pinfunction "CLR_1") (pintype "input"))
      (node (ref "E39") (pin "10") (pinfunction "PRE_10") (pintype "input"))
      (node (ref "E48") (pin "6") (pinfunction "O_6") (pintype "output"))
      (node (ref "E50") (pin "16") (pinfunction "CLR_16") (pintype "input"))
      (node (ref "E52") (pin "1") (pinfunction "CLR_1") (pintype "input"))
    )
    (net (code "243") (name "~{CLR_SYN}") (class "Default")
      (node (ref "E34") (pin "9") (pinfunction "I1_9") (pintype "input"))
      (node (ref "E52") (pin "9") (pinfunction "Q_9") (pintype "output"))
    )
    (net (code "244") (name "~{DATA0}") (class "Default")
      (node (ref "E8") (pin "3") (pinfunction "F0_3") (pintype "open_collector"))
      (node (ref "OMNIBUS") (pin "AR1") (pinfunction "1_AR1") (pintype "bidirectional"))
    )
    (net (code "245") (name "~{DATA1}") (class "Default")
      (node (ref "E8") (pin "4") (pinfunction "F1_4") (pintype "open_collector"))
      (node (ref "OMNIBUS") (pin "AS1") (pinfunction "1_AS1") (pintype "bidirectional"))
    )
    (net (code "246") (name "~{DATA2}") (class "Default")
      (node (ref "E8") (pin "12") (pinfunction "F2_12") (pintype "open_collector"))
      (node (ref "OMNIBUS") (pin "AU1") (pinfunction "1_AU1") (pintype "bidirectional"))
    )
    (net (code "247") (name "~{DATA3}") (class "Default")
      (node (ref "E8") (pin "13") (pinfunction "F3_13") (pintype "open_collector"))
      (node (ref "OMNIBUS") (pin "AV1") (pinfunction "1_AV1") (pintype "bidirectional"))
    )
    (net (code "248") (name "~{DATA4}") (class "Default")
      (node (ref "E22") (pin "3") (pinfunction "F0_3") (pintype "open_collector"))
      (node (ref "OMNIBUS") (pin "BR1") (pinfunction "1_BR1") (pintype "bidirectional"))
    )
    (net (code "249") (name "~{DATA5}") (class "Default")
      (node (ref "E22") (pin "4") (pinfunction "F1_4") (pintype "open_collector"))
      (node (ref "OMNIBUS") (pin "BS1") (pinfunction "1_BS1") (pintype "bidirectional"))
    )
    (net (code "250") (name "~{DATA6}") (class "Default")
      (node (ref "E22") (pin "12") (pinfunction "F2_12") (pintype "open_collector"))
      (node (ref "OMNIBUS") (pin "BU1") (pinfunction "1_BU1") (pintype "bidirectional"))
    )
    (net (code "251") (name "~{DATA7}") (class "Default")
      (node (ref "E22") (pin "13") (pinfunction "F3_13") (pintype "open_collector"))
      (node (ref "E35") (pin "12") (pinfunction "I1_12") (pintype "input"))
      (node (ref "OMNIBUS") (pin "BV1") (pinfunction "1_BV1") (pintype "bidirectional"))
    )
    (net (code "252") (name "~{DATA8}") (class "Default")
      (node (ref "E49") (pin "3") (pinfunction "F0_3") (pintype "open_collector"))
      (node (ref "OMNIBUS") (pin "DR1") (pinfunction "1_DR1") (pintype "bidirectional"))
    )
    (net (code "253") (name "~{DATA9}") (class "Default")
      (node (ref "E49") (pin "4") (pinfunction "F1_4") (pintype "open_collector"))
      (node (ref "OMNIBUS") (pin "DS1") (pinfunction "1_DS1") (pintype "bidirectional"))
    )
    (net (code "254") (name "~{DATA10}") (class "Default")
      (node (ref "E49") (pin "12") (pinfunction "F2_12") (pintype "open_collector"))
      (node (ref "OMNIBUS") (pin "DU1") (pinfunction "1_DU1") (pintype "bidirectional"))
    )
    (net (code "255") (name "~{DATA11}") (class "Default")
      (node (ref "E49") (pin "13") (pinfunction "F3_13") (pintype "open_collector"))
      (node (ref "OMNIBUS") (pin "DV1") (pinfunction "1_DV1") (pintype "bidirectional"))
    )
    (net (code "256") (name "~{DATA_RQST_LATE}") (class "Default")
      (node (ref "E39") (pin "6") (pinfunction "~{Q}_6") (pintype "output"))
      (node (ref "E47") (pin "9") (pinfunction "I0_9") (pintype "input"))
    )
    (net (code "257") (name "~{DATA_STATE}") (class "Default")
      (node (ref "E47") (pin "13") (pinfunction "I2_13") (pintype "input"))
      (node (ref "J") (pin "M2") (pinfunction "P_M2") (pintype "passive"))
    )
    (net (code "258") (name "~{DB_CONT1}") (class "Default")
      (node (ref "E12") (pin "13") (pinfunction "~{Q}_13") (pintype "output"))
      (node (ref "E13") (pin "6") (pinfunction "I1_6") (pintype "input"))
      (node (ref "H") (pin "V1") (pinfunction "P_V1") (pintype "passive"))
    )
    (net (code "259") (name "~{DB_CONT2}") (class "Default")
      (node (ref "E12") (pin "8") (pinfunction "~{Q}_8") (pintype "output"))
      (node (ref "E13") (pin "9") (pinfunction "I1_9") (pintype "input"))
    )
    (net (code "260") (name "~{DB_CONT3}") (class "Default")
      (node (ref "E13") (pin "11") (pinfunction "I0_11") (pintype "input"))
      (node (ref "E14") (pin "14") (pinfunction "~{Q}_14") (pintype "output"))
    )
    (net (code "261") (name "~{DB_CONT4}") (class "Default")
      (node (ref "E14") (pin "10") (pinfunction "~{Q}_10") (pintype "output"))
      (node (ref "E39") (pin "2") (pinfunction "D_2") (pintype "input"))
      (node (ref "R15") (pin "1") (pinfunction "1_1") (pintype "passive"))
    )
    (net (code "262") (name "~{DEVICE_RK}") (class "Default")
      (node (ref "E31") (pin "4") (pinfunction "O_4") (pintype "output"))
      (node (ref "E37") (pin "2") (pinfunction "D_2") (pintype "input"))
    )
    (net (code "263") (name "~{DONE_FLAG}") (class "Default")
      (node (ref "E39") (pin "9") (pinfunction "Q_9") (pintype "output"))
      (node (ref "E54") (pin "2") (pinfunction "I1_2") (pintype "input"))
    )
    (net (code "264") (name "~{DSK_CAPACITY_EX}") (class "Default")
      (node (ref "E45") (pin "12") (pinfunction "I0_12") (pintype "input"))
      (node (ref "J") (pin "K1") (pinfunction "P_K1") (pintype "passive"))
      (node (ref "R1") (pin "2") (pinfunction "2_2") (pintype "passive"))
      (node (ref "R2") (pin "1") (pinfunction "1_1") (pintype "passive"))
    )
    (net (code "265") (name "~{DSK_FILE_RDY}") (class "Default")
      (node (ref "E22") (pin "1") (pinfunction "A0_1") (pintype "input"))
      (node (ref "H") (pin "E1") (pinfunction "P_E1") (pintype "passive"))
    )
    (net (code "266") (name "~{DSK_WRT_STATUS}") (class "Default")
      (node (ref "E51") (pin "12") (pinfunction "I1_12") (pintype "input"))
      (node (ref "J") (pin "D2") (pinfunction "P_D2") (pintype "passive"))
      (node (ref "R3") (pin "1") (pinfunction "1_1") (pintype "passive"))
      (node (ref "R4") (pin "2") (pinfunction "2_2") (pintype "passive"))
    )
    (net (code "267") (name "~{ENAB_RK_DATA}") (class "Default")
      (node (ref "E22") (pin "9") (pinfunction "S0_9") (pintype "input"))
      (node (ref "E31") (pin "6") (pinfunction "O_6") (pintype "output"))
      (node (ref "E49") (pin "9") (pinfunction "S0_9") (pintype "input"))
      (node (ref "E8") (pin "9") (pinfunction "S0_9") (pintype "input"))
    )
    (net (code "268") (name "~{END_STATE}") (class "Default")
      (node (ref "E51") (pin "6") (pinfunction "I1_6") (pintype "input"))
      (node (ref "J") (pin "J2") (pinfunction "P_J2") (pintype "passive"))
    )
    (net (code "269") (name "~{ERROR_CLR}") (class "Default")
      (node (ref "E53") (pin "13") (pinfunction "O_13") (pintype "output"))
      (node (ref "J") (pin "D1") (pinfunction "P_D1") (pintype "passive"))
    )
    (net (code "270") (name "~{ERROR_FL}") (class "Default")
      (node (ref "E53") (pin "10") (pinfunction "O_10") (pintype "output"))
      (node (ref "E54") (pin "1") (pinfunction "I0_1") (pintype "input"))
    )
    (net (code "271") (name "~{HI_RD_CLK}") (class "Default")
      (node (ref "E11") (pin "12") (pinfunction "I0_12") (pintype "input"))
      (node (ref "E27") (pin "10") (pinfunction "O_10") (pintype "output"))
    )
    (net (code "272") (name "~{IDLE}") (class "Default")
      (node (ref "E19") (pin "6") (pinfunction "I1_6") (pintype "input"))
      (node (ref "E48") (pin "10") (pinfunction "I1_10") (pintype "input"))
      (node (ref "J") (pin "N1") (pinfunction "P_N1") (pintype "passive"))
    )
    (net (code "273") (name "~{INTERNAL_IO}") (class "Default")
      (node (ref "E36") (pin "10") (pinfunction "O_10") (pintype "open_collector"))
      (node (ref "OMNIBUS") (pin "CL1") (pinfunction "1_CL1") (pintype "bidirectional"))
    )
    (net (code "274") (name "~{INT_RQST}") (class "Default")
      (node (ref "E36") (pin "4") (pinfunction "O_4") (pintype "open_collector"))
      (node (ref "OMNIBUS") (pin "CP1") (pinfunction "1_CP1") (pintype "bidirectional"))
    )
    (net (code "275") (name "~{IO_PAUSE}") (class "Default")
      (node (ref "E1") (pin "11") (pinfunction "I5_11") (pintype "input"))
      (node (ref "E35") (pin "10") (pinfunction "I1_10") (pintype "input"))
      (node (ref "OMNIBUS") (pin "CD1") (pinfunction "1_CD1") (pintype "bidirectional"))
    )
    (net (code "276") (name "~{LD_DB_AC}") (class "Default")
      (node (ref "E21") (pin "9") (pinfunction "I_9") (pintype "input"))
      (node (ref "E33") (pin "13") (pinfunction "I1_13") (pintype "input"))
      (node (ref "E40") (pin "10") (pinfunction "I1_10") (pintype "input"))
      (node (ref "E54") (pin "11") (pinfunction "O_11") (pintype "output"))
    )
    (net (code "277") (name "~{LO_MAIN_SHFT}") (class "Default")
      (node (ref "E20") (pin "1") (pinfunction "I0_1") (pintype "input"))
      (node (ref "H") (pin "P1") (pinfunction "P_P1") (pintype "passive"))
    )
    (net (code "278") (name "~{MAIN}") (class "Default")
      (node (ref "E40") (pin "1") (pinfunction "I0_1") (pintype "input"))
      (node (ref "E47") (pin "1") (pinfunction "I0_1") (pintype "input"))
      (node (ref "J") (pin "E1") (pinfunction "P_E1") (pintype "passive"))
    )
    (net (code "279") (name "~{MAK}") (class "Default")
      (node (ref "E28") (pin "12") (pinfunction "I1_12") (pintype "input"))
      (node (ref "H") (pin "J1") (pinfunction "P_J1") (pintype "passive"))
    )
    (net (code "280") (name "~{MD0}") (class "Default")
      (node (ref "E2") (pin "7") (pinfunction "I1_7") (pintype "input"))
      (node (ref "OMNIBUS") (pin "AK1") (pinfunction "1_AK1") (pintype "bidirectional"))
    )
    (net (code "281") (name "~{MD1}") (class "Default")
      (node (ref "E2") (pin "9") (pinfunction "I0_9") (pintype "input"))
      (node (ref "OMNIBUS") (pin "AL1") (pinfunction "1_AL1") (pintype "bidirectional"))
    )
    (net (code "282") (name "~{MD2}") (class "Default")
      (node (ref "E2") (pin "4") (pinfunction "I0_4") (pintype "input"))
      (node (ref "OMNIBUS") (pin "AM1") (pinfunction "1_AM1") (pintype "bidirectional"))
    )
    (net (code "283") (name "~{MD3}") (class "Default")
      (node (ref "E1") (pin "12") (pinfunction "I6_12") (pintype "input"))
      (node (ref "E2") (pin "12") (pinfunction "I1_12") (pintype "input"))
      (node (ref "OMNIBUS") (pin "AP1") (pinfunction "1_AP1") (pintype "bidirectional"))
    )
    (net (code "284") (name "~{MD4}") (class "Default")
      (node (ref "E1") (pin "10") (pinfunction "I4_10") (pintype "input"))
      (node (ref "E15") (pin "7") (pinfunction "I1_7") (pintype "input"))
      (node (ref "OMNIBUS") (pin "BK1") (pinfunction "1_BK1") (pintype "bidirectional"))
    )
    (net (code "285") (name "~{MD5}") (class "Default")
      (node (ref "E1") (pin "9") (pinfunction "I3_9") (pintype "input"))
      (node (ref "E15") (pin "9") (pinfunction "I0_9") (pintype "input"))
      (node (ref "OMNIBUS") (pin "BL1") (pinfunction "1_BL1") (pintype "bidirectional"))
    )
    (net (code "286") (name "~{MD6}") (class "Default")
      (node (ref "E15") (pin "4") (pinfunction "I0_4") (pintype "input"))
      (node (ref "OMNIBUS") (pin "BM1") (pinfunction "1_BM1") (pintype "bidirectional"))
      (node (ref "W2W5") (pin "1") (pinfunction "1_1") (pintype "passive"))
    )
    (net (code "287") (name "~{MD7}") (class "Default")
      (node (ref "E15") (pin "12") (pinfunction "I1_12") (pintype "input"))
      (node (ref "OMNIBUS") (pin "BP1") (pinfunction "1_BP1") (pintype "bidirectional"))
      (node (ref "W1W4") (pin "3") (pinfunction "3_3") (pintype "passive"))
    )
    (net (code "288") (name "~{MD8}") (class "Default")
      (node (ref "E42") (pin "7") (pinfunction "I1_7") (pintype "input"))
      (node (ref "OMNIBUS") (pin "DK1") (pinfunction "1_DK1") (pintype "bidirectional"))
      (node (ref "W3W6") (pin "3") (pinfunction "3_3") (pintype "passive"))
    )
    (net (code "289") (name "~{MD9}") (class "Default")
      (node (ref "E42") (pin "9") (pinfunction "I0_9") (pintype "input"))
      (node (ref "OMNIBUS") (pin "DL1") (pinfunction "1_DL1") (pintype "bidirectional"))
    )
    (net (code "290") (name "~{MD10}") (class "Default")
      (node (ref "E42") (pin "4") (pinfunction "I0_4") (pintype "input"))
      (node (ref "OMNIBUS") (pin "DM1") (pinfunction "1_DM1") (pintype "bidirectional"))
    )
    (net (code "291") (name "~{MD11}") (class "Default")
      (node (ref "E42") (pin "12") (pinfunction "I1_12") (pintype "input"))
      (node (ref "OMNIBUS") (pin "DP1") (pinfunction "1_DP1") (pintype "bidirectional"))
    )
    (net (code "292") (name "~{MD_RD_BUFF}") (class "Default")
      (node (ref "E15") (pin "10") (pinfunction "I1_10") (pintype "input"))
      (node (ref "E15") (pin "6") (pinfunction "I0_6") (pintype "input"))
      (node (ref "E19") (pin "11") (pinfunction "I0_11") (pintype "input"))
      (node (ref "E2") (pin "10") (pinfunction "I1_10") (pintype "input"))
      (node (ref "E2") (pin "11") (pinfunction "I0_11") (pintype "input"))
      (node (ref "E2") (pin "5") (pinfunction "I1_5") (pintype "input"))
      (node (ref "E2") (pin "6") (pinfunction "I0_6") (pintype "input"))
      (node (ref "E20") (pin "6") (pinfunction "O_6") (pintype "output"))
      (node (ref "E27") (pin "3") (pinfunction "I_3") (pintype "input"))
      (node (ref "E47") (pin "2") (pinfunction "I1_2") (pintype "input"))
      (node (ref "R9") (pin "1") (pinfunction "1_1") (pintype "passive"))
    )
    (net (code "293") (name "~{MD_RK}") (class "Default")
      (node (ref "E42") (pin "10") (pinfunction "I1_10") (pintype "input"))
      (node (ref "E42") (pin "11") (pinfunction "I0_11") (pintype "input"))
      (node (ref "E42") (pin "5") (pinfunction "I1_5") (pintype "input"))
      (node (ref "E51") (pin "1") (pinfunction "O_1") (pintype "output"))
      (node (ref "R11") (pin "1") (pinfunction "1_1") (pintype "passive"))
    )
    (net (code "294") (name "~{NOT_EQUAL}") (class "Default")
      (node (ref "E51") (pin "5") (pinfunction "I0_5") (pintype "input"))
      (node (ref "E51") (pin "8") (pinfunction "I0_8") (pintype "input"))
      (node (ref "J") (pin "F2") (pinfunction "P_F2") (pintype "passive"))
    )
    (net (code "295") (name "~{RDY_S{slash}R{slash}W}") (class "Default")
      (node (ref "E8") (pin "6") (pinfunction "A1_6") (pintype "input"))
      (node (ref "H") (pin "U1") (pinfunction "P_U1") (pintype "passive"))
    )
    (net (code "296") (name "~{RD_BRK}") (class "Default")
      (node (ref "E28") (pin "9") (pinfunction "I1_9") (pintype "input"))
      (node (ref "H") (pin "L2") (pinfunction "P_L2") (pintype "passive"))
    )
    (net (code "297") (name "~{RK_DATA0}") (class "Default")
      (node (ref "E16") (pin "6") (pinfunction "O_6") (pintype "output"))
      (node (ref "E8") (pin "2") (pinfunction "B0_2") (pintype "input"))
    )
    (net (code "298") (name "~{RK_DATA1}") (class "Default")
      (node (ref "E16") (pin "4") (pinfunction "O_4") (pintype "output"))
      (node (ref "E8") (pin "5") (pinfunction "B1_5") (pintype "input"))
    )
    (net (code "299") (name "~{RK_DATA2}") (class "Default")
      (node (ref "E16") (pin "10") (pinfunction "O_10") (pintype "output"))
      (node (ref "E8") (pin "11") (pinfunction "B2_11") (pintype "input"))
    )
    (net (code "300") (name "~{RK_DATA3}") (class "Default")
      (node (ref "E16") (pin "8") (pinfunction "O_8") (pintype "output"))
      (node (ref "E8") (pin "14") (pinfunction "B3_14") (pintype "input"))
    )
    (net (code "301") (name "~{RK_DATA4}") (class "Default")
      (node (ref "E22") (pin "2") (pinfunction "B0_2") (pintype "input"))
      (node (ref "E23") (pin "8") (pinfunction "O_8") (pintype "output"))
    )
    (net (code "302") (name "~{RK_DATA5}") (class "Default")
      (node (ref "E16") (pin "12") (pinfunction "O_12") (pintype "output"))
      (node (ref "E22") (pin "5") (pinfunction "B1_5") (pintype "input"))
    )
    (net (code "303") (name "~{RK_DATA6}") (class "Default")
      (node (ref "E16") (pin "2") (pinfunction "O_2") (pintype "output"))
      (node (ref "E22") (pin "11") (pinfunction "B2_11") (pintype "input"))
    )
    (net (code "304") (name "~{RK_DATA7}") (class "Default")
      (node (ref "E22") (pin "14") (pinfunction "B3_14") (pintype "input"))
      (node (ref "E23") (pin "10") (pinfunction "O_10") (pintype "output"))
    )
    (net (code "305") (name "~{RK_DATA8}") (class "Default")
      (node (ref "E23") (pin "2") (pinfunction "O_2") (pintype "output"))
      (node (ref "E49") (pin "2") (pinfunction "B0_2") (pintype "input"))
    )
    (net (code "306") (name "~{RK_DATA9}") (class "Default")
      (node (ref "E23") (pin "6") (pinfunction "O_6") (pintype "output"))
      (node (ref "E49") (pin "5") (pinfunction "B1_5") (pintype "input"))
    )
    (net (code "307") (name "~{RK_DATA10}") (class "Default")
      (node (ref "E23") (pin "4") (pinfunction "O_4") (pintype "output"))
      (node (ref "E49") (pin "11") (pinfunction "B2_11") (pintype "input"))
    )
    (net (code "308") (name "~{RK_DATA11}") (class "Default")
      (node (ref "E23") (pin "12") (pinfunction "O_12") (pintype "output"))
      (node (ref "E49") (pin "14") (pinfunction "B3_14") (pintype "input"))
    )
    (net (code "309") (name "~{SECTOR_SEEK}") (class "Default")
      (node (ref "E51") (pin "9") (pinfunction "I1_9") (pintype "input"))
      (node (ref "J") (pin "F1") (pinfunction "P_F1") (pintype "passive"))
    )
    (net (code "310") (name "~{SET_IDLE_PL}") (class "Default")
      (node (ref "E46") (pin "13") (pinfunction "I1_13") (pintype "input"))
      (node (ref "E46") (pin "3") (pinfunction "O_3") (pintype "output"))
      (node (ref "J") (pin "J1") (pinfunction "P_J1") (pintype "passive"))
    )
    (net (code "311") (name "~{SHFT_WRT_BUFF}") (class "Default")
      (node (ref "E20") (pin "2") (pinfunction "I1_2") (pintype "input"))
      (node (ref "H") (pin "R2") (pinfunction "P_R2") (pintype "passive"))
    )
    (net (code "312") (name "~{SKIP}") (class "Default")
      (node (ref "E36") (pin "1") (pinfunction "O_1") (pintype "open_collector"))
      (node (ref "OMNIBUS") (pin "CS1") (pinfunction "1_CS1") (pintype "bidirectional"))
    )
    (net (code "313") (name "~{TEST_CLK}") (class "Default")
      (node (ref "E7") (pin "12") (pinfunction "~{Q}_12") (pintype "output"))
      (node (ref "E7") (pin "2") (pinfunction "B_2") (pintype "input"))
    )
    (net (code "314") (name "~{TS3}") (class "Default")
      (node (ref "OMNIBUS") (pin "CM2") (pinfunction "1_CM2") (pintype "bidirectional"))
    )
    (net (code "315") (name "~{WRT_BRK}") (class "Default")
      (node (ref "E28") (pin "2") (pinfunction "I0_2") (pintype "input"))
      (node (ref "H") (pin "H1") (pinfunction "P_H1") (pintype "passive"))
    )
    (net (code "316") (name "~{WRT_BUFF_SHFT}") (class "Default")
      (node (ref "E17") (pin "9") (pinfunction "CK1_9") (pintype "input"))
      (node (ref "E24") (pin "9") (pinfunction "CK1_9") (pintype "input"))
      (node (ref "E31") (pin "8") (pinfunction "O_8") (pintype "output"))
      (node (ref "E9") (pin "9") (pinfunction "CK1_9") (pintype "input"))
    )
    (net (code "317") (name "~{WRT_CMD}") (class "Default")
      (node (ref "E11") (pin "13") (pinfunction "I1_13") (pintype "input"))
      (node (ref "E11") (pin "2") (pinfunction "I1_2") (pintype "input"))
      (node (ref "E51") (pin "11") (pinfunction "I0_11") (pintype "input"))
      (node (ref "J") (pin "E2") (pinfunction "P_E2") (pintype "passive"))
    )
    (net (code "318") (name "~{WRT_LOCK_ER}") (class "Default")
      (node (ref "E52") (pin "6") (pinfunction "~{Q}_6") (pintype "output"))
    )
    (net (code "319") (name "~{WT_BUFF_DATA}") (class "Default")
      (node (ref "E21") (pin "13") (pinfunction "I_13") (pintype "input"))
      (node (ref "E33") (pin "12") (pinfunction "I0_12") (pintype "input"))
      (node (ref "H") (pin "D2") (pinfunction "P_D2") (pintype "passive"))
    )
  )
)
